# ElectronOnAStick-V1.net
KiCad netlist of a schematic drawn in EAGLE
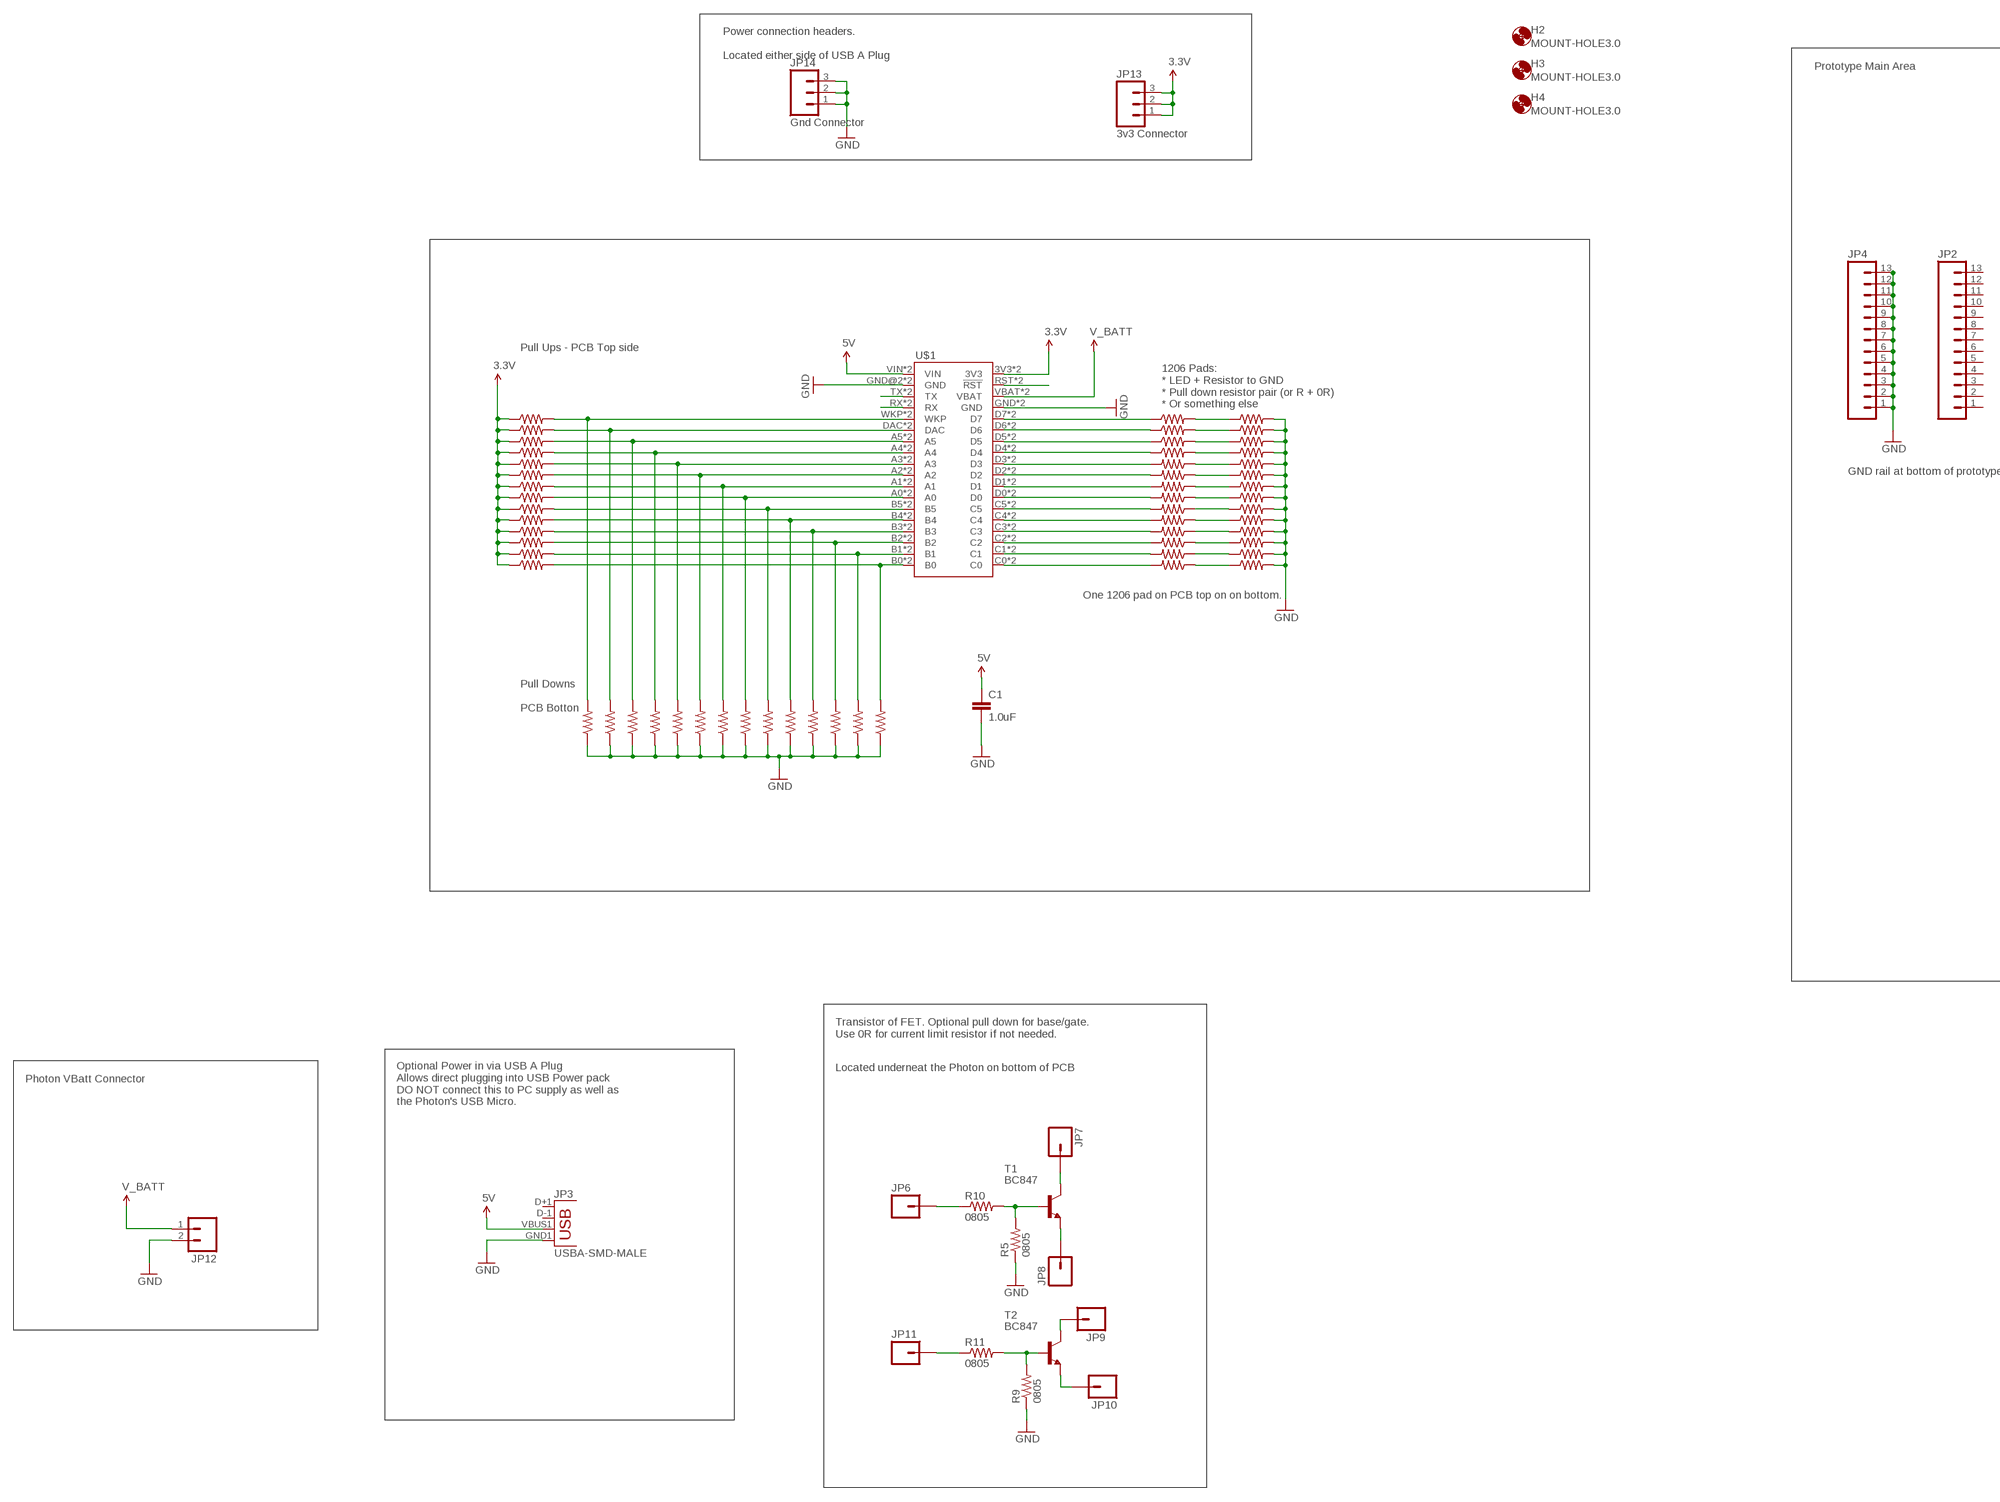
[diagram p0: schematic, sheet 1, part 1 of 2]
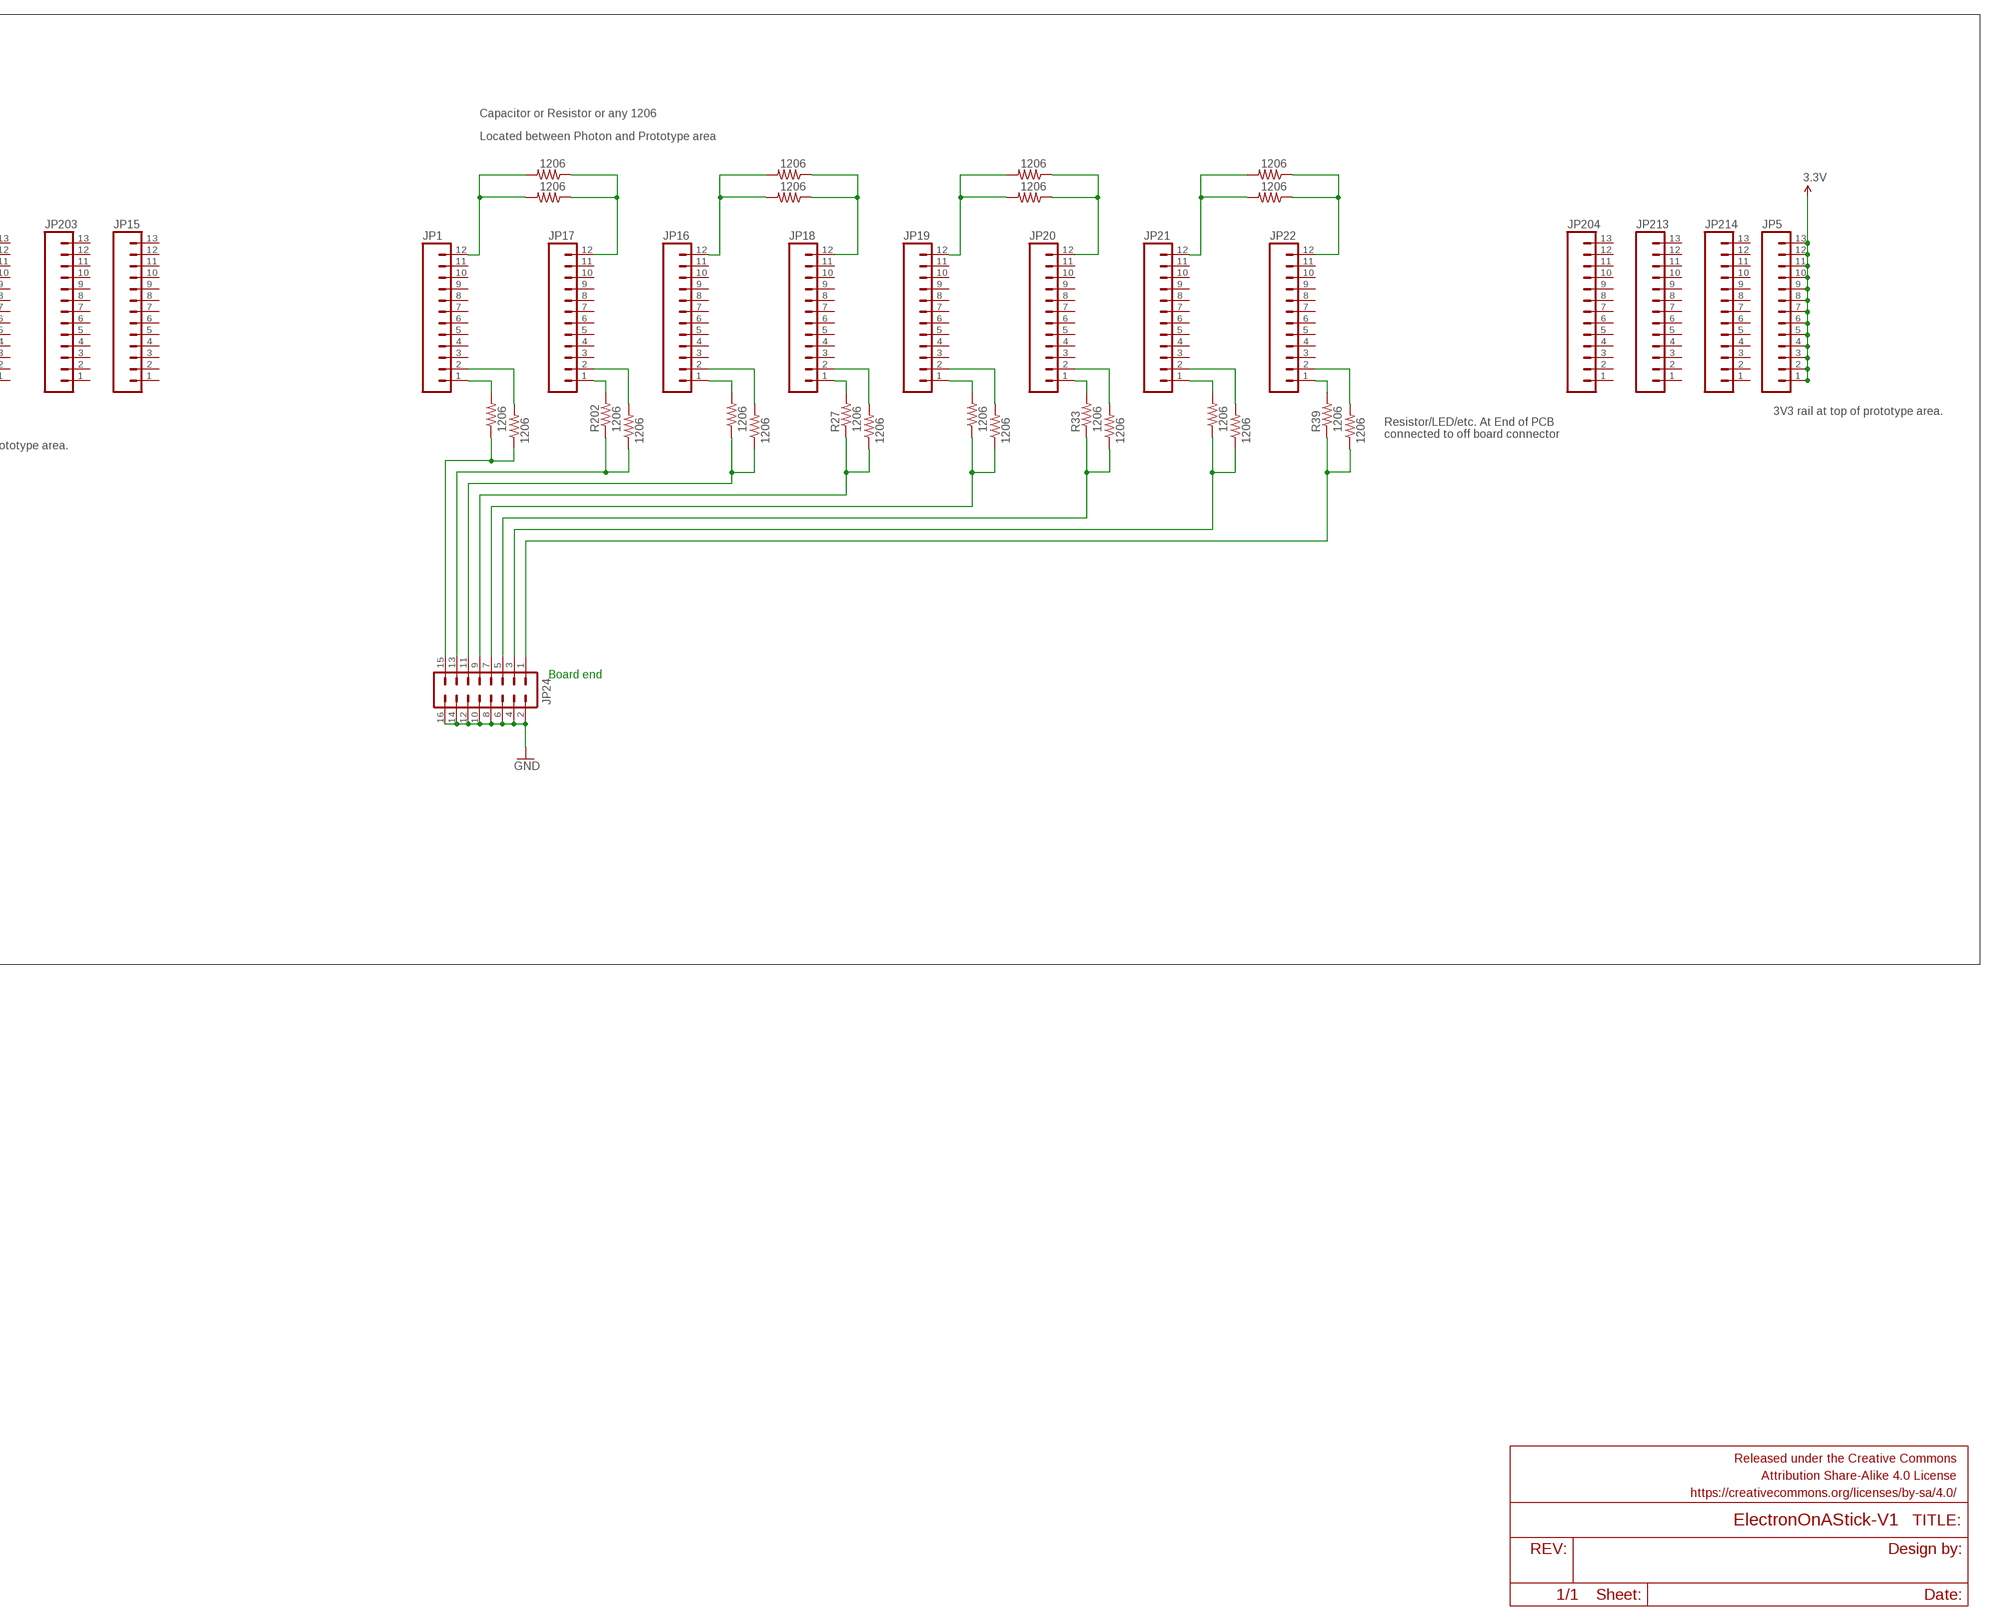
[diagram p1: schematic, sheet 1, part 2 of 2]

(export (version "E")
  (design (tool "Eeschema 10.0.6"))
  (components
    (comp (ref "C1")
      (value "1.0uF")
      (footprint "eagle-import:0805-CAP")
      (libsource (lib "eagle-import") (part "1.0UF-25V-+80/-20(0805){dblquote}"))
    )
    (comp (ref "FRAME1")
      (value "FRAME-LEDGER")
      (footprint "eagle-import:CREATIVE_COMMONS")
      (libsource (lib "eagle-import") (part "FRAME-LEDGER"))
    )
    (comp (ref "H2")
      (value "MOUNT-HOLE3.0")
      (footprint "eagle-import:3,0")
      (libsource (lib "eagle-import") (part "MOUNT-HOLE3.0"))
    )
    (comp (ref "H3")
      (value "MOUNT-HOLE3.0")
      (footprint "eagle-import:3,0")
      (libsource (lib "eagle-import") (part "MOUNT-HOLE3.0"))
    )
    (comp (ref "H4")
      (value "MOUNT-HOLE3.0")
      (footprint "eagle-import:3,0")
      (libsource (lib "eagle-import") (part "MOUNT-HOLE3.0"))
    )
    (comp (ref "JP1")
      (value "M12PTH")
      (footprint "eagle-import:1X12")
      (libsource (lib "eagle-import") (part "M12PTH"))
    )
    (comp (ref "JP2")
      (value "M13")
      (footprint "eagle-import:1X13")
      (libsource (lib "eagle-import") (part "M13"))
    )
    (comp (ref "JP3")
      (value "USBA-SMD-MALE")
      (footprint "eagle-import:USB-A-SMT-MALE")
      (libsource (lib "eagle-import") (part "USBA-SMD-MALE"))
    )
    (comp (ref "JP4")
      (value "M13")
      (footprint "eagle-import:1X13")
      (libsource (lib "eagle-import") (part "M13"))
    )
    (comp (ref "JP5")
      (value "M13")
      (footprint "eagle-import:1X13")
      (libsource (lib "eagle-import") (part "M13"))
    )
    (comp (ref "JP6")
      (value "M01PTH")
      (footprint "eagle-import:1X01")
      (libsource (lib "eagle-import") (part "M01PTH"))
    )
    (comp (ref "JP7")
      (value "M01PTH")
      (footprint "eagle-import:1X01")
      (libsource (lib "eagle-import") (part "M01PTH"))
    )
    (comp (ref "JP8")
      (value "M01PTH")
      (footprint "eagle-import:1X01")
      (libsource (lib "eagle-import") (part "M01PTH"))
    )
    (comp (ref "JP9")
      (value "M01PTH")
      (footprint "eagle-import:1X01")
      (libsource (lib "eagle-import") (part "M01PTH"))
    )
    (comp (ref "JP10")
      (value "M01PTH")
      (footprint "eagle-import:1X01")
      (libsource (lib "eagle-import") (part "M01PTH"))
    )
    (comp (ref "JP11")
      (value "M01PTH")
      (footprint "eagle-import:1X01")
      (libsource (lib "eagle-import") (part "M01PTH"))
    )
    (comp (ref "JP12")
      (value "M02JST-PTH-2")
      (footprint "eagle-import:JST-2-PTH")
      (libsource (lib "eagle-import") (part "M02JST-PTH-2"))
    )
    (comp (ref "JP13")
      (value "3v3 Connector")
      (footprint "eagle-import:1X03")
      (libsource (lib "eagle-import") (part "M03PTH"))
    )
    (comp (ref "JP14")
      (value "Gnd Connector")
      (footprint "eagle-import:1X03")
      (libsource (lib "eagle-import") (part "M03PTH"))
    )
    (comp (ref "JP15")
      (value "M13")
      (footprint "eagle-import:1X13")
      (libsource (lib "eagle-import") (part "M13"))
    )
    (comp (ref "JP16")
      (value "M12PTH")
      (footprint "eagle-import:1X12")
      (libsource (lib "eagle-import") (part "M12PTH"))
    )
    (comp (ref "JP17")
      (value "M12PTH")
      (footprint "eagle-import:1X12")
      (libsource (lib "eagle-import") (part "M12PTH"))
    )
    (comp (ref "JP18")
      (value "M12PTH")
      (footprint "eagle-import:1X12")
      (libsource (lib "eagle-import") (part "M12PTH"))
    )
    (comp (ref "JP19")
      (value "M12PTH")
      (footprint "eagle-import:1X12")
      (libsource (lib "eagle-import") (part "M12PTH"))
    )
    (comp (ref "JP20")
      (value "M12PTH")
      (footprint "eagle-import:1X12")
      (libsource (lib "eagle-import") (part "M12PTH"))
    )
    (comp (ref "JP21")
      (value "M12PTH")
      (footprint "eagle-import:1X12")
      (libsource (lib "eagle-import") (part "M12PTH"))
    )
    (comp (ref "JP22")
      (value "M12PTH")
      (footprint "eagle-import:1X12")
      (libsource (lib "eagle-import") (part "M12PTH"))
    )
    (comp (ref "JP24")
      (value "M08X2")
      (footprint "eagle-import:2X8")
      (libsource (lib "eagle-import") (part "M08X2"))
    )
    (comp (ref "JP203")
      (value "M13")
      (footprint "eagle-import:1X13")
      (libsource (lib "eagle-import") (part "M13"))
    )
    (comp (ref "JP204")
      (value "M13")
      (footprint "eagle-import:1X13")
      (libsource (lib "eagle-import") (part "M13"))
    )
    (comp (ref "JP213")
      (value "M13")
      (footprint "eagle-import:1X13")
      (libsource (lib "eagle-import") (part "M13"))
    )
    (comp (ref "JP214")
      (value "M13")
      (footprint "eagle-import:1X13")
      (libsource (lib "eagle-import") (part "M13"))
    )
    (comp (ref "R1")
      (value "1206")
      (footprint "eagle-import:1206")
      (libsource (lib "eagle-import") (part "RESISTOR1206"))
    )
    (comp (ref "R2")
      (value "1206")
      (footprint "eagle-import:1206")
      (libsource (lib "eagle-import") (part "RESISTOR1206"))
    )
    (comp (ref "R3")
      (value "1206")
      (footprint "eagle-import:1206")
      (libsource (lib "eagle-import") (part "RESISTOR1206"))
    )
    (comp (ref "R4")
      (value "1206")
      (footprint "eagle-import:1206")
      (libsource (lib "eagle-import") (part "RESISTOR1206"))
    )
    (comp (ref "R5")
      (value "0805")
      (footprint "eagle-import:0805")
      (libsource (lib "eagle-import") (part "RESISTOR0805-RES"))
    )
    (comp (ref "R6")
      (value "1206")
      (footprint "eagle-import:1206")
      (libsource (lib "eagle-import") (part "RESISTOR1206"))
    )
    (comp (ref "R7")
      (value "1206")
      (footprint "eagle-import:1206")
      (libsource (lib "eagle-import") (part "RESISTOR1206"))
    )
    (comp (ref "R8")
      (value "1206")
      (footprint "eagle-import:1206")
      (libsource (lib "eagle-import") (part "RESISTOR1206"))
    )
    (comp (ref "R9")
      (value "0805")
      (footprint "eagle-import:0805")
      (libsource (lib "eagle-import") (part "RESISTOR0805-RES"))
    )
    (comp (ref "R10")
      (value "0805")
      (footprint "eagle-import:0805")
      (libsource (lib "eagle-import") (part "RESISTOR0805-RES"))
    )
    (comp (ref "R11")
      (value "0805")
      (footprint "eagle-import:0805")
      (libsource (lib "eagle-import") (part "RESISTOR0805-RES"))
    )
    (comp (ref "R12")
      (value "1206")
      (footprint "eagle-import:1206")
      (libsource (lib "eagle-import") (part "RESISTOR1206"))
    )
    (comp (ref "R13")
      (value "1206")
      (footprint "eagle-import:1206")
      (libsource (lib "eagle-import") (part "RESISTOR1206"))
    )
    (comp (ref "R14")
      (value "1206")
      (footprint "eagle-import:1206")
      (libsource (lib "eagle-import") (part "RESISTOR1206"))
    )
    (comp (ref "R15")
      (value "1206")
      (footprint "eagle-import:1206")
      (libsource (lib "eagle-import") (part "RESISTOR1206"))
    )
    (comp (ref "R16")
      (value "1206")
      (footprint "eagle-import:1206")
      (libsource (lib "eagle-import") (part "RESISTOR1206"))
    )
    (comp (ref "R17")
      (value "1206")
      (footprint "eagle-import:1206")
      (libsource (lib "eagle-import") (part "RESISTOR1206"))
    )
    (comp (ref "R18")
      (value "1206")
      (footprint "eagle-import:1206")
      (libsource (lib "eagle-import") (part "RESISTOR1206"))
    )
    (comp (ref "R19")
      (value "1206")
      (footprint "eagle-import:1206")
      (libsource (lib "eagle-import") (part "RESISTOR1206"))
    )
    (comp (ref "R20")
      (value "1206")
      (footprint "eagle-import:1206")
      (libsource (lib "eagle-import") (part "RESISTOR1206"))
    )
    (comp (ref "R21")
      (value "1206")
      (footprint "eagle-import:1206")
      (libsource (lib "eagle-import") (part "RESISTOR1206"))
    )
    (comp (ref "R22")
      (value "1206")
      (footprint "eagle-import:1206")
      (libsource (lib "eagle-import") (part "RESISTOR1206"))
    )
    (comp (ref "R23")
      (value "1206")
      (footprint "eagle-import:1206")
      (libsource (lib "eagle-import") (part "RESISTOR1206"))
    )
    (comp (ref "R24")
      (value "1206")
      (footprint "eagle-import:1206")
      (libsource (lib "eagle-import") (part "RESISTOR1206"))
    )
    (comp (ref "R25")
      (value "1206")
      (footprint "eagle-import:1206")
      (libsource (lib "eagle-import") (part "RESISTOR1206"))
    )
    (comp (ref "R26")
      (value "1206")
      (footprint "eagle-import:1206")
      (libsource (lib "eagle-import") (part "RESISTOR1206"))
    )
    (comp (ref "R27")
      (value "1206")
      (footprint "eagle-import:1206")
      (libsource (lib "eagle-import") (part "RESISTOR1206"))
    )
    (comp (ref "R28")
      (value "1206")
      (footprint "eagle-import:1206")
      (libsource (lib "eagle-import") (part "RESISTOR1206"))
    )
    (comp (ref "R29")
      (value "1206")
      (footprint "eagle-import:1206")
      (libsource (lib "eagle-import") (part "RESISTOR1206"))
    )
    (comp (ref "R30")
      (value "1206")
      (footprint "eagle-import:1206")
      (libsource (lib "eagle-import") (part "RESISTOR1206"))
    )
    (comp (ref "R31")
      (value "1206")
      (footprint "eagle-import:1206")
      (libsource (lib "eagle-import") (part "RESISTOR1206"))
    )
    (comp (ref "R32")
      (value "1206")
      (footprint "eagle-import:1206")
      (libsource (lib "eagle-import") (part "RESISTOR1206"))
    )
    (comp (ref "R33")
      (value "1206")
      (footprint "eagle-import:1206")
      (libsource (lib "eagle-import") (part "RESISTOR1206"))
    )
    (comp (ref "R34")
      (value "1206")
      (footprint "eagle-import:1206")
      (libsource (lib "eagle-import") (part "RESISTOR1206"))
    )
    (comp (ref "R35")
      (value "1206")
      (footprint "eagle-import:1206")
      (libsource (lib "eagle-import") (part "RESISTOR1206"))
    )
    (comp (ref "R36")
      (value "1206")
      (footprint "eagle-import:1206")
      (libsource (lib "eagle-import") (part "RESISTOR1206"))
    )
    (comp (ref "R37")
      (value "1206")
      (footprint "eagle-import:1206")
      (libsource (lib "eagle-import") (part "RESISTOR1206"))
    )
    (comp (ref "R38")
      (value "1206")
      (footprint "eagle-import:1206")
      (libsource (lib "eagle-import") (part "RESISTOR1206"))
    )
    (comp (ref "R39")
      (value "1206")
      (footprint "eagle-import:1206")
      (libsource (lib "eagle-import") (part "RESISTOR1206"))
    )
    (comp (ref "R40")
      (value "1206")
      (footprint "eagle-import:1206")
      (libsource (lib "eagle-import") (part "RESISTOR1206"))
    )
    (comp (ref "R41")
      (value "1206")
      (footprint "eagle-import:1206")
      (libsource (lib "eagle-import") (part "RESISTOR1206"))
    )
    (comp (ref "R42")
      (value "1206")
      (footprint "eagle-import:1206")
      (libsource (lib "eagle-import") (part "RESISTOR1206"))
    )
    (comp (ref "R43")
      (value "1206")
      (footprint "eagle-import:1206")
      (libsource (lib "eagle-import") (part "RESISTOR1206"))
    )
    (comp (ref "R44")
      (value "1206")
      (footprint "eagle-import:1206")
      (libsource (lib "eagle-import") (part "RESISTOR1206"))
    )
    (comp (ref "R45")
      (value "1206")
      (footprint "eagle-import:1206")
      (libsource (lib "eagle-import") (part "RESISTOR1206"))
    )
    (comp (ref "R46")
      (value "1206")
      (footprint "eagle-import:1206")
      (libsource (lib "eagle-import") (part "RESISTOR1206"))
    )
    (comp (ref "R47")
      (value "1206")
      (footprint "eagle-import:1206")
      (libsource (lib "eagle-import") (part "RESISTOR1206"))
    )
    (comp (ref "R48")
      (value "1206")
      (footprint "eagle-import:1206")
      (libsource (lib "eagle-import") (part "RESISTOR1206"))
    )
    (comp (ref "R49")
      (value "1206")
      (footprint "eagle-import:1206")
      (libsource (lib "eagle-import") (part "RESISTOR1206"))
    )
    (comp (ref "R50")
      (value "1206")
      (footprint "eagle-import:1206")
      (libsource (lib "eagle-import") (part "RESISTOR1206"))
    )
    (comp (ref "R51")
      (value "1206")
      (footprint "eagle-import:1206")
      (libsource (lib "eagle-import") (part "RESISTOR1206"))
    )
    (comp (ref "R52")
      (value "1206")
      (footprint "eagle-import:1206")
      (libsource (lib "eagle-import") (part "RESISTOR1206"))
    )
    (comp (ref "R53")
      (value "1206")
      (footprint "eagle-import:1206")
      (libsource (lib "eagle-import") (part "RESISTOR1206"))
    )
    (comp (ref "R54")
      (value "1206")
      (footprint "eagle-import:1206")
      (libsource (lib "eagle-import") (part "RESISTOR1206"))
    )
    (comp (ref "R55")
      (value "1206")
      (footprint "eagle-import:1206")
      (libsource (lib "eagle-import") (part "RESISTOR1206"))
    )
    (comp (ref "R56")
      (value "1206")
      (footprint "eagle-import:1206")
      (libsource (lib "eagle-import") (part "RESISTOR1206"))
    )
    (comp (ref "R57")
      (value "1206")
      (footprint "eagle-import:1206")
      (libsource (lib "eagle-import") (part "RESISTOR1206"))
    )
    (comp (ref "R58")
      (value "1206")
      (footprint "eagle-import:1206")
      (libsource (lib "eagle-import") (part "RESISTOR1206"))
    )
    (comp (ref "R59")
      (value "1206")
      (footprint "eagle-import:1206")
      (libsource (lib "eagle-import") (part "RESISTOR1206"))
    )
    (comp (ref "R60")
      (value "1206")
      (footprint "eagle-import:1206")
      (libsource (lib "eagle-import") (part "RESISTOR1206"))
    )
    (comp (ref "R61")
      (value "1206")
      (footprint "eagle-import:1206")
      (libsource (lib "eagle-import") (part "RESISTOR1206"))
    )
    (comp (ref "R62")
      (value "1206")
      (footprint "eagle-import:1206")
      (libsource (lib "eagle-import") (part "RESISTOR1206"))
    )
    (comp (ref "R63")
      (value "1206")
      (footprint "eagle-import:1206")
      (libsource (lib "eagle-import") (part "RESISTOR1206"))
    )
    (comp (ref "R64")
      (value "1206")
      (footprint "eagle-import:1206")
      (libsource (lib "eagle-import") (part "RESISTOR1206"))
    )
    (comp (ref "R65")
      (value "1206")
      (footprint "eagle-import:1206")
      (libsource (lib "eagle-import") (part "RESISTOR1206"))
    )
    (comp (ref "R66")
      (value "1206")
      (footprint "eagle-import:1206")
      (libsource (lib "eagle-import") (part "RESISTOR1206"))
    )
    (comp (ref "R67")
      (value "1206")
      (footprint "eagle-import:1206")
      (libsource (lib "eagle-import") (part "RESISTOR1206"))
    )
    (comp (ref "R68")
      (value "1206")
      (footprint "eagle-import:1206")
      (libsource (lib "eagle-import") (part "RESISTOR1206"))
    )
    (comp (ref "R69")
      (value "1206")
      (footprint "eagle-import:1206")
      (libsource (lib "eagle-import") (part "RESISTOR1206"))
    )
    (comp (ref "R70")
      (value "1206")
      (footprint "eagle-import:1206")
      (libsource (lib "eagle-import") (part "RESISTOR1206"))
    )
    (comp (ref "R201")
      (value "1206")
      (footprint "eagle-import:1206")
      (libsource (lib "eagle-import") (part "RESISTOR1206"))
    )
    (comp (ref "R202")
      (value "1206")
      (footprint "eagle-import:1206")
      (libsource (lib "eagle-import") (part "RESISTOR1206"))
    )
    (comp (ref "R313")
      (value "1206")
      (footprint "eagle-import:1206")
      (libsource (lib "eagle-import") (part "RESISTOR1206"))
    )
    (comp (ref "R314")
      (value "1206")
      (footprint "eagle-import:1206")
      (libsource (lib "eagle-import") (part "RESISTOR1206"))
    )
    (comp (ref "R315")
      (value "1206")
      (footprint "eagle-import:1206")
      (libsource (lib "eagle-import") (part "RESISTOR1206"))
    )
    (comp (ref "R316")
      (value "1206")
      (footprint "eagle-import:1206")
      (libsource (lib "eagle-import") (part "RESISTOR1206"))
    )
    (comp (ref "R317")
      (value "1206")
      (footprint "eagle-import:1206")
      (libsource (lib "eagle-import") (part "RESISTOR1206"))
    )
    (comp (ref "R318")
      (value "1206")
      (footprint "eagle-import:1206")
      (libsource (lib "eagle-import") (part "RESISTOR1206"))
    )
    (comp (ref "R319")
      (value "1206")
      (footprint "eagle-import:1206")
      (libsource (lib "eagle-import") (part "RESISTOR1206"))
    )
    (comp (ref "R320")
      (value "1206")
      (footprint "eagle-import:1206")
      (libsource (lib "eagle-import") (part "RESISTOR1206"))
    )
    (comp (ref "R410")
      (value "1206")
      (footprint "eagle-import:1206")
      (libsource (lib "eagle-import") (part "RESISTOR1206"))
    )
    (comp (ref "R411")
      (value "1206")
      (footprint "eagle-import:1206")
      (libsource (lib "eagle-import") (part "RESISTOR1206"))
    )
    (comp (ref "R412")
      (value "1206")
      (footprint "eagle-import:1206")
      (libsource (lib "eagle-import") (part "RESISTOR1206"))
    )
    (comp (ref "R413")
      (value "1206")
      (footprint "eagle-import:1206")
      (libsource (lib "eagle-import") (part "RESISTOR1206"))
    )
    (comp (ref "T1")
      (value "BC847")
      (footprint "eagle-import:SOT23")
      (libsource (lib "eagle-import") (part "BC847"))
    )
    (comp (ref "T2")
      (value "BC847")
      (footprint "eagle-import:SOT23")
      (libsource (lib "eagle-import") (part "BC847"))
    )
    (comp (ref "U$1")
      (value "ELECTRONDUALNAMED")
      (footprint "eagle-import:ELECTRON_SIMPLE_SILK_NAMES_DUAL")
      (libsource (lib "eagle-import") (part "ELECTRONDUALNAMED"))
    )
  )
  (nets
    (net (code "1") (name "3.3V") (class "Default")
      (node (ref "JP13") (pin "1") (pinfunction "1_1") (pintype "passive"))
      (node (ref "JP13") (pin "2") (pinfunction "2_2") (pintype "passive"))
      (node (ref "JP13") (pin "3") (pinfunction "3_3") (pintype "passive"))
      (node (ref "JP5") (pin "1") (pinfunction "1_1") (pintype "passive"))
      (node (ref "JP5") (pin "10") (pinfunction "10_10") (pintype "passive"))
      (node (ref "JP5") (pin "11") (pinfunction "11_11") (pintype "passive"))
      (node (ref "JP5") (pin "12") (pinfunction "12_12") (pintype "passive"))
      (node (ref "JP5") (pin "13") (pinfunction "13_13") (pintype "passive"))
      (node (ref "JP5") (pin "2") (pinfunction "2_2") (pintype "passive"))
      (node (ref "JP5") (pin "3") (pinfunction "3_3") (pintype "passive"))
      (node (ref "JP5") (pin "4") (pinfunction "4_4") (pintype "passive"))
      (node (ref "JP5") (pin "5") (pinfunction "5_5") (pintype "passive"))
      (node (ref "JP5") (pin "6") (pinfunction "6_6") (pintype "passive"))
      (node (ref "JP5") (pin "7") (pinfunction "7_7") (pintype "passive"))
      (node (ref "JP5") (pin "8") (pinfunction "8_8") (pintype "passive"))
      (node (ref "JP5") (pin "9") (pinfunction "9_9") (pintype "passive"))
      (node (ref "R1") (pin "1") (pinfunction "1_1") (pintype "passive"))
      (node (ref "R12") (pin "1") (pinfunction "1_1") (pintype "passive"))
      (node (ref "R2") (pin "1") (pinfunction "1_1") (pintype "passive"))
      (node (ref "R3") (pin "1") (pinfunction "1_1") (pintype "passive"))
      (node (ref "R4") (pin "1") (pinfunction "1_1") (pintype "passive"))
      (node (ref "R45") (pin "1") (pinfunction "1_1") (pintype "passive"))
      (node (ref "R46") (pin "1") (pinfunction "1_1") (pintype "passive"))
      (node (ref "R47") (pin "1") (pinfunction "1_1") (pintype "passive"))
      (node (ref "R48") (pin "1") (pinfunction "1_1") (pintype "passive"))
      (node (ref "R49") (pin "1") (pinfunction "1_1") (pintype "passive"))
      (node (ref "R6") (pin "1") (pinfunction "1_1") (pintype "passive"))
      (node (ref "R67") (pin "1") (pinfunction "1_1") (pintype "passive"))
      (node (ref "R68") (pin "1") (pinfunction "1_1") (pintype "passive"))
      (node (ref "R7") (pin "1") (pinfunction "1_1") (pintype "passive"))
      (node (ref "U$1") (pin "3V3") (pinfunction "3V3_3V3") (pintype "power_in"))
      (node (ref "U$1") (pin "3V3_1") (pinfunction "3V3_3V3_1") (pintype "power_in"))
    )
    (net (code "2") (name "5V") (class "Default")
      (node (ref "C1") (pin "1") (pinfunction "1_1") (pintype "passive"))
      (node (ref "JP3") (pin "VBUS1") (pinfunction "VBUS_VBUS1") (pintype "bidirectional"))
      (node (ref "U$1") (pin "VIN") (pinfunction "VIN_VIN") (pintype "power_in"))
      (node (ref "U$1") (pin "VIN_1B") (pinfunction "VIN_VIN_1B") (pintype "power_in"))
    )
    (net (code "3") (name "GND") (class "Default")
      (node (ref "C1") (pin "2") (pinfunction "2_2") (pintype "passive"))
      (node (ref "JP12") (pin "2") (pinfunction "2_2") (pintype "passive"))
      (node (ref "JP14") (pin "1") (pinfunction "1_1") (pintype "passive"))
      (node (ref "JP14") (pin "2") (pinfunction "2_2") (pintype "passive"))
      (node (ref "JP14") (pin "3") (pinfunction "3_3") (pintype "passive"))
      (node (ref "JP24") (pin "10") (pinfunction "10_10") (pintype "passive"))
      (node (ref "JP24") (pin "12") (pinfunction "12_12") (pintype "passive"))
      (node (ref "JP24") (pin "14") (pinfunction "14_14") (pintype "passive"))
      (node (ref "JP24") (pin "16") (pinfunction "16_16") (pintype "passive"))
      (node (ref "JP24") (pin "2") (pinfunction "2_2") (pintype "passive"))
      (node (ref "JP24") (pin "4") (pinfunction "4_4") (pintype "passive"))
      (node (ref "JP24") (pin "6") (pinfunction "6_6") (pintype "passive"))
      (node (ref "JP24") (pin "8") (pinfunction "8_8") (pintype "passive"))
      (node (ref "JP3") (pin "GND1") (pinfunction "GND_GND1") (pintype "bidirectional"))
      (node (ref "JP4") (pin "1") (pinfunction "1_1") (pintype "passive"))
      (node (ref "JP4") (pin "10") (pinfunction "10_10") (pintype "passive"))
      (node (ref "JP4") (pin "11") (pinfunction "11_11") (pintype "passive"))
      (node (ref "JP4") (pin "12") (pinfunction "12_12") (pintype "passive"))
      (node (ref "JP4") (pin "13") (pinfunction "13_13") (pintype "passive"))
      (node (ref "JP4") (pin "2") (pinfunction "2_2") (pintype "passive"))
      (node (ref "JP4") (pin "3") (pinfunction "3_3") (pintype "passive"))
      (node (ref "JP4") (pin "4") (pinfunction "4_4") (pintype "passive"))
      (node (ref "JP4") (pin "5") (pinfunction "5_5") (pintype "passive"))
      (node (ref "JP4") (pin "6") (pinfunction "6_6") (pintype "passive"))
      (node (ref "JP4") (pin "7") (pinfunction "7_7") (pintype "passive"))
      (node (ref "JP4") (pin "8") (pinfunction "8_8") (pintype "passive"))
      (node (ref "JP4") (pin "9") (pinfunction "9_9") (pintype "passive"))
      (node (ref "R13") (pin "1") (pinfunction "1_1") (pintype "passive"))
      (node (ref "R14") (pin "1") (pinfunction "1_1") (pintype "passive"))
      (node (ref "R15") (pin "2") (pinfunction "2_2") (pintype "passive"))
      (node (ref "R16") (pin "2") (pinfunction "2_2") (pintype "passive"))
      (node (ref "R17") (pin "2") (pinfunction "2_2") (pintype "passive"))
      (node (ref "R18") (pin "2") (pinfunction "2_2") (pintype "passive"))
      (node (ref "R19") (pin "1") (pinfunction "1_1") (pintype "passive"))
      (node (ref "R20") (pin "1") (pinfunction "1_1") (pintype "passive"))
      (node (ref "R21") (pin "1") (pinfunction "1_1") (pintype "passive"))
      (node (ref "R22") (pin "1") (pinfunction "1_1") (pintype "passive"))
      (node (ref "R410") (pin "2") (pinfunction "2_2") (pintype "passive"))
      (node (ref "R411") (pin "2") (pinfunction "2_2") (pintype "passive"))
      (node (ref "R412") (pin "2") (pinfunction "2_2") (pintype "passive"))
      (node (ref "R413") (pin "2") (pinfunction "2_2") (pintype "passive"))
      (node (ref "R5") (pin "1") (pinfunction "1_1") (pintype "passive"))
      (node (ref "R50") (pin "1") (pinfunction "1_1") (pintype "passive"))
      (node (ref "R51") (pin "1") (pinfunction "1_1") (pintype "passive"))
      (node (ref "R52") (pin "1") (pinfunction "1_1") (pintype "passive"))
      (node (ref "R53") (pin "1") (pinfunction "1_1") (pintype "passive"))
      (node (ref "R54") (pin "1") (pinfunction "1_1") (pintype "passive"))
      (node (ref "R55") (pin "2") (pinfunction "2_2") (pintype "passive"))
      (node (ref "R56") (pin "2") (pinfunction "2_2") (pintype "passive"))
      (node (ref "R57") (pin "2") (pinfunction "2_2") (pintype "passive"))
      (node (ref "R58") (pin "2") (pinfunction "2_2") (pintype "passive"))
      (node (ref "R59") (pin "2") (pinfunction "2_2") (pintype "passive"))
      (node (ref "R60") (pin "2") (pinfunction "2_2") (pintype "passive"))
      (node (ref "R69") (pin "1") (pinfunction "1_1") (pintype "passive"))
      (node (ref "R70") (pin "1") (pinfunction "1_1") (pintype "passive"))
      (node (ref "R8") (pin "1") (pinfunction "1_1") (pintype "passive"))
      (node (ref "R9") (pin "1") (pinfunction "1_1") (pintype "passive"))
      (node (ref "U$1") (pin "GND") (pinfunction "GND_GND") (pintype "power_in"))
      (node (ref "U$1") (pin "GND@2") (pinfunction "GND_GND@2") (pintype "power_in"))
      (node (ref "U$1") (pin "GND_1") (pinfunction "GND_GND_1") (pintype "power_in"))
      (node (ref "U$1") (pin "GND_1B") (pinfunction "GND_GND_1B") (pintype "power_in"))
    )
    (net (code "4") (name "Net-(JP1-Pad1)") (class "Default")
      (node (ref "JP1") (pin "1") (pinfunction "1_1") (pintype "passive"))
      (node (ref "R201") (pin "2") (pinfunction "2_2") (pintype "passive"))
    )
    (net (code "5") (name "Net-(JP1-Pad2)") (class "Default")
      (node (ref "JP1") (pin "2") (pinfunction "2_2") (pintype "passive"))
      (node (ref "R23") (pin "2") (pinfunction "2_2") (pintype "passive"))
    )
    (net (code "6") (name "Net-(JP1-Pad12)") (class "Default")
      (node (ref "JP1") (pin "12") (pinfunction "12_12") (pintype "passive"))
      (node (ref "R24") (pin "2") (pinfunction "2_2") (pintype "passive"))
      (node (ref "R25") (pin "2") (pinfunction "2_2") (pintype "passive"))
    )
    (net (code "7") (name "Net-(JP6-Pad1)") (class "Default")
      (node (ref "JP6") (pin "1") (pinfunction "1_1") (pintype "passive"))
      (node (ref "R10") (pin "1") (pinfunction "1_1") (pintype "passive"))
    )
    (net (code "8") (name "Net-(JP11-Pad1)") (class "Default")
      (node (ref "JP11") (pin "1") (pinfunction "1_1") (pintype "passive"))
      (node (ref "R11") (pin "1") (pinfunction "1_1") (pintype "passive"))
    )
    (net (code "9") (name "Net-(JP16-Pad1)") (class "Default")
      (node (ref "JP16") (pin "1") (pinfunction "1_1") (pintype "passive"))
      (node (ref "R28") (pin "2") (pinfunction "2_2") (pintype "passive"))
    )
    (net (code "10") (name "Net-(JP16-Pad2)") (class "Default")
      (node (ref "JP16") (pin "2") (pinfunction "2_2") (pintype "passive"))
      (node (ref "R29") (pin "2") (pinfunction "2_2") (pintype "passive"))
    )
    (net (code "11") (name "Net-(JP16-Pad12)") (class "Default")
      (node (ref "JP16") (pin "12") (pinfunction "12_12") (pintype "passive"))
      (node (ref "R30") (pin "2") (pinfunction "2_2") (pintype "passive"))
      (node (ref "R31") (pin "2") (pinfunction "2_2") (pintype "passive"))
    )
    (net (code "12") (name "Net-(JP17-Pad1)") (class "Default")
      (node (ref "JP17") (pin "1") (pinfunction "1_1") (pintype "passive"))
      (node (ref "R202") (pin "2") (pinfunction "2_2") (pintype "passive"))
    )
    (net (code "13") (name "Net-(JP17-Pad2)") (class "Default")
      (node (ref "JP17") (pin "2") (pinfunction "2_2") (pintype "passive"))
      (node (ref "R26") (pin "2") (pinfunction "2_2") (pintype "passive"))
    )
    (net (code "14") (name "Net-(JP17-Pad12)") (class "Default")
      (node (ref "JP17") (pin "12") (pinfunction "12_12") (pintype "passive"))
      (node (ref "R24") (pin "1") (pinfunction "1_1") (pintype "passive"))
      (node (ref "R25") (pin "1") (pinfunction "1_1") (pintype "passive"))
    )
    (net (code "15") (name "Net-(JP18-Pad1)") (class "Default")
      (node (ref "JP18") (pin "1") (pinfunction "1_1") (pintype "passive"))
      (node (ref "R27") (pin "2") (pinfunction "2_2") (pintype "passive"))
    )
    (net (code "16") (name "Net-(JP18-Pad2)") (class "Default")
      (node (ref "JP18") (pin "2") (pinfunction "2_2") (pintype "passive"))
      (node (ref "R32") (pin "2") (pinfunction "2_2") (pintype "passive"))
    )
    (net (code "17") (name "Net-(JP18-Pad12)") (class "Default")
      (node (ref "JP18") (pin "12") (pinfunction "12_12") (pintype "passive"))
      (node (ref "R30") (pin "1") (pinfunction "1_1") (pintype "passive"))
      (node (ref "R31") (pin "1") (pinfunction "1_1") (pintype "passive"))
    )
    (net (code "18") (name "Net-(JP19-Pad1)") (class "Default")
      (node (ref "JP19") (pin "1") (pinfunction "1_1") (pintype "passive"))
      (node (ref "R34") (pin "2") (pinfunction "2_2") (pintype "passive"))
    )
    (net (code "19") (name "Net-(JP19-Pad2)") (class "Default")
      (node (ref "JP19") (pin "2") (pinfunction "2_2") (pintype "passive"))
      (node (ref "R35") (pin "2") (pinfunction "2_2") (pintype "passive"))
    )
    (net (code "20") (name "Net-(JP19-Pad12)") (class "Default")
      (node (ref "JP19") (pin "12") (pinfunction "12_12") (pintype "passive"))
      (node (ref "R36") (pin "2") (pinfunction "2_2") (pintype "passive"))
      (node (ref "R37") (pin "2") (pinfunction "2_2") (pintype "passive"))
    )
    (net (code "21") (name "Net-(JP20-Pad1)") (class "Default")
      (node (ref "JP20") (pin "1") (pinfunction "1_1") (pintype "passive"))
      (node (ref "R33") (pin "2") (pinfunction "2_2") (pintype "passive"))
    )
    (net (code "22") (name "Net-(JP20-Pad2)") (class "Default")
      (node (ref "JP20") (pin "2") (pinfunction "2_2") (pintype "passive"))
      (node (ref "R38") (pin "2") (pinfunction "2_2") (pintype "passive"))
    )
    (net (code "23") (name "Net-(JP20-Pad12)") (class "Default")
      (node (ref "JP20") (pin "12") (pinfunction "12_12") (pintype "passive"))
      (node (ref "R36") (pin "1") (pinfunction "1_1") (pintype "passive"))
      (node (ref "R37") (pin "1") (pinfunction "1_1") (pintype "passive"))
    )
    (net (code "24") (name "Net-(JP21-Pad1)") (class "Default")
      (node (ref "JP21") (pin "1") (pinfunction "1_1") (pintype "passive"))
      (node (ref "R40") (pin "2") (pinfunction "2_2") (pintype "passive"))
    )
    (net (code "25") (name "Net-(JP21-Pad2)") (class "Default")
      (node (ref "JP21") (pin "2") (pinfunction "2_2") (pintype "passive"))
      (node (ref "R41") (pin "2") (pinfunction "2_2") (pintype "passive"))
    )
    (net (code "26") (name "Net-(JP21-Pad12)") (class "Default")
      (node (ref "JP21") (pin "12") (pinfunction "12_12") (pintype "passive"))
      (node (ref "R42") (pin "2") (pinfunction "2_2") (pintype "passive"))
      (node (ref "R43") (pin "2") (pinfunction "2_2") (pintype "passive"))
    )
    (net (code "27") (name "Net-(JP22-Pad1)") (class "Default")
      (node (ref "JP22") (pin "1") (pinfunction "1_1") (pintype "passive"))
      (node (ref "R39") (pin "2") (pinfunction "2_2") (pintype "passive"))
    )
    (net (code "28") (name "Net-(JP22-Pad2)") (class "Default")
      (node (ref "JP22") (pin "2") (pinfunction "2_2") (pintype "passive"))
      (node (ref "R44") (pin "2") (pinfunction "2_2") (pintype "passive"))
    )
    (net (code "29") (name "Net-(JP22-Pad12)") (class "Default")
      (node (ref "JP22") (pin "12") (pinfunction "12_12") (pintype "passive"))
      (node (ref "R42") (pin "1") (pinfunction "1_1") (pintype "passive"))
      (node (ref "R43") (pin "1") (pinfunction "1_1") (pintype "passive"))
    )
    (net (code "30") (name "Net-(JP24-Pad1)") (class "Default")
      (node (ref "JP24") (pin "1") (pinfunction "1_1") (pintype "passive"))
      (node (ref "R39") (pin "1") (pinfunction "1_1") (pintype "passive"))
      (node (ref "R44") (pin "1") (pinfunction "1_1") (pintype "passive"))
    )
    (net (code "31") (name "Net-(JP24-Pad3)") (class "Default")
      (node (ref "JP24") (pin "3") (pinfunction "3_3") (pintype "passive"))
      (node (ref "R40") (pin "1") (pinfunction "1_1") (pintype "passive"))
      (node (ref "R41") (pin "1") (pinfunction "1_1") (pintype "passive"))
    )
    (net (code "32") (name "Net-(JP24-Pad5)") (class "Default")
      (node (ref "JP24") (pin "5") (pinfunction "5_5") (pintype "passive"))
      (node (ref "R33") (pin "1") (pinfunction "1_1") (pintype "passive"))
      (node (ref "R38") (pin "1") (pinfunction "1_1") (pintype "passive"))
    )
    (net (code "33") (name "Net-(JP24-Pad7)") (class "Default")
      (node (ref "JP24") (pin "7") (pinfunction "7_7") (pintype "passive"))
      (node (ref "R34") (pin "1") (pinfunction "1_1") (pintype "passive"))
      (node (ref "R35") (pin "1") (pinfunction "1_1") (pintype "passive"))
    )
    (net (code "34") (name "Net-(JP24-Pad9)") (class "Default")
      (node (ref "JP24") (pin "9") (pinfunction "9_9") (pintype "passive"))
      (node (ref "R27") (pin "1") (pinfunction "1_1") (pintype "passive"))
      (node (ref "R32") (pin "1") (pinfunction "1_1") (pintype "passive"))
    )
    (net (code "35") (name "Net-(JP24-Pad11)") (class "Default")
      (node (ref "JP24") (pin "11") (pinfunction "11_11") (pintype "passive"))
      (node (ref "R28") (pin "1") (pinfunction "1_1") (pintype "passive"))
      (node (ref "R29") (pin "1") (pinfunction "1_1") (pintype "passive"))
    )
    (net (code "36") (name "Net-(JP24-Pad13)") (class "Default")
      (node (ref "JP24") (pin "13") (pinfunction "13_13") (pintype "passive"))
      (node (ref "R202") (pin "1") (pinfunction "1_1") (pintype "passive"))
      (node (ref "R26") (pin "1") (pinfunction "1_1") (pintype "passive"))
    )
    (net (code "37") (name "Net-(JP24-Pad15)") (class "Default")
      (node (ref "JP24") (pin "15") (pinfunction "15_15") (pintype "passive"))
      (node (ref "R201") (pin "1") (pinfunction "1_1") (pintype "passive"))
      (node (ref "R23") (pin "1") (pinfunction "1_1") (pintype "passive"))
    )
    (net (code "38") (name "Net-(R1-Pad2)") (class "Default")
      (node (ref "R1") (pin "2") (pinfunction "2_2") (pintype "passive"))
      (node (ref "R13") (pin "2") (pinfunction "2_2") (pintype "passive"))
      (node (ref "U$1") (pin "A4") (pinfunction "A4_A4") (pintype "bidirectional"))
      (node (ref "U$1") (pin "A4_1") (pinfunction "A4_A4_1") (pintype "bidirectional"))
    )
    (net (code "39") (name "Net-(R12-Pad2)") (class "Default")
      (node (ref "R12") (pin "2") (pinfunction "2_2") (pintype "passive"))
      (node (ref "R8") (pin "2") (pinfunction "2_2") (pintype "passive"))
      (node (ref "U$1") (pin "A5") (pinfunction "A5_A5") (pintype "bidirectional"))
      (node (ref "U$1") (pin "A5_1") (pinfunction "A5_A5_1") (pintype "bidirectional"))
    )
    (net (code "40") (name "Net-(R14-Pad2)") (class "Default")
      (node (ref "R14") (pin "2") (pinfunction "2_2") (pintype "passive"))
      (node (ref "R2") (pin "2") (pinfunction "2_2") (pintype "passive"))
      (node (ref "U$1") (pin "A3") (pinfunction "A3_A3") (pintype "bidirectional"))
      (node (ref "U$1") (pin "A3_1") (pinfunction "A3_A3_1") (pintype "bidirectional"))
    )
    (net (code "41") (name "Net-(R15-Pad1)") (class "Default")
      (node (ref "R15") (pin "1") (pinfunction "1_1") (pintype "passive"))
      (node (ref "R316") (pin "1") (pinfunction "1_1") (pintype "passive"))
    )
    (net (code "42") (name "Net-(R16-Pad1)") (class "Default")
      (node (ref "R16") (pin "1") (pinfunction "1_1") (pintype "passive"))
      (node (ref "R315") (pin "1") (pinfunction "1_1") (pintype "passive"))
    )
    (net (code "43") (name "Net-(R17-Pad1)") (class "Default")
      (node (ref "R17") (pin "1") (pinfunction "1_1") (pintype "passive"))
      (node (ref "R314") (pin "1") (pinfunction "1_1") (pintype "passive"))
    )
    (net (code "44") (name "Net-(R18-Pad1)") (class "Default")
      (node (ref "R18") (pin "1") (pinfunction "1_1") (pintype "passive"))
      (node (ref "R313") (pin "1") (pinfunction "1_1") (pintype "passive"))
    )
    (net (code "45") (name "Net-(R19-Pad2)") (class "Default")
      (node (ref "R19") (pin "2") (pinfunction "2_2") (pintype "passive"))
      (node (ref "R3") (pin "2") (pinfunction "2_2") (pintype "passive"))
      (node (ref "U$1") (pin "A2") (pinfunction "A2_A2") (pintype "bidirectional"))
      (node (ref "U$1") (pin "A2_1") (pinfunction "A2_A2_1") (pintype "bidirectional"))
    )
    (net (code "46") (name "Net-(R20-Pad2)") (class "Default")
      (node (ref "R20") (pin "2") (pinfunction "2_2") (pintype "passive"))
      (node (ref "R4") (pin "2") (pinfunction "2_2") (pintype "passive"))
      (node (ref "U$1") (pin "A1") (pinfunction "A1_A1") (pintype "bidirectional"))
      (node (ref "U$1") (pin "A1_1") (pinfunction "A1_A1_1") (pintype "bidirectional"))
    )
    (net (code "47") (name "Net-(R21-Pad2)") (class "Default")
      (node (ref "R21") (pin "2") (pinfunction "2_2") (pintype "passive"))
      (node (ref "R6") (pin "2") (pinfunction "2_2") (pintype "passive"))
      (node (ref "U$1") (pin "A0") (pinfunction "A0_A0") (pintype "bidirectional"))
      (node (ref "U$1") (pin "A0_1") (pinfunction "A0_A0_1") (pintype "bidirectional"))
    )
    (net (code "48") (name "Net-(R22-Pad2)") (class "Default")
      (node (ref "R22") (pin "2") (pinfunction "2_2") (pintype "passive"))
      (node (ref "R47") (pin "2") (pinfunction "2_2") (pintype "passive"))
      (node (ref "U$1") (pin "B2") (pinfunction "B2_B2") (pintype "bidirectional"))
      (node (ref "U$1") (pin "B2_1") (pinfunction "B2_B2_1") (pintype "bidirectional"))
    )
    (net (code "49") (name "Net-(R45-Pad2)") (class "Default")
      (node (ref "R45") (pin "2") (pinfunction "2_2") (pintype "passive"))
      (node (ref "R51") (pin "2") (pinfunction "2_2") (pintype "passive"))
      (node (ref "U$1") (pin "B4") (pinfunction "B4_B4") (pintype "bidirectional"))
      (node (ref "U$1") (pin "B4_1") (pinfunction "B4_B4_1") (pintype "bidirectional"))
    )
    (net (code "50") (name "Net-(R46-Pad2)") (class "Default")
      (node (ref "R46") (pin "2") (pinfunction "2_2") (pintype "passive"))
      (node (ref "R52") (pin "2") (pinfunction "2_2") (pintype "passive"))
      (node (ref "U$1") (pin "B3") (pinfunction "B3_B3") (pintype "bidirectional"))
      (node (ref "U$1") (pin "B3_1") (pinfunction "B3_B3_1") (pintype "bidirectional"))
    )
    (net (code "51") (name "Net-(R48-Pad2)") (class "Default")
      (node (ref "R48") (pin "2") (pinfunction "2_2") (pintype "passive"))
      (node (ref "R53") (pin "2") (pinfunction "2_2") (pintype "passive"))
      (node (ref "U$1") (pin "B1") (pinfunction "B1_B1") (pintype "bidirectional"))
      (node (ref "U$1") (pin "B1_1") (pinfunction "B1_B1_1") (pintype "bidirectional"))
    )
    (net (code "52") (name "Net-(R49-Pad2)") (class "Default")
      (node (ref "R49") (pin "2") (pinfunction "2_2") (pintype "passive"))
      (node (ref "R54") (pin "2") (pinfunction "2_2") (pintype "passive"))
      (node (ref "U$1") (pin "B0") (pinfunction "B0_B0") (pintype "bidirectional"))
      (node (ref "U$1") (pin "B0_1") (pinfunction "B0_B0_1") (pintype "bidirectional"))
    )
    (net (code "53") (name "Net-(R50-Pad2)") (class "Default")
      (node (ref "R50") (pin "2") (pinfunction "2_2") (pintype "passive"))
      (node (ref "R7") (pin "2") (pinfunction "2_2") (pintype "passive"))
      (node (ref "U$1") (pin "B5") (pinfunction "B5_B5") (pintype "bidirectional"))
      (node (ref "U$1") (pin "B5_1") (pinfunction "B5_B5_1") (pintype "bidirectional"))
    )
    (net (code "54") (name "Net-(R55-Pad1)") (class "Default")
      (node (ref "R55") (pin "1") (pinfunction "1_1") (pintype "passive"))
      (node (ref "R61") (pin "1") (pinfunction "1_1") (pintype "passive"))
    )
    (net (code "55") (name "Net-(R56-Pad1)") (class "Default")
      (node (ref "R56") (pin "1") (pinfunction "1_1") (pintype "passive"))
      (node (ref "R62") (pin "1") (pinfunction "1_1") (pintype "passive"))
    )
    (net (code "56") (name "Net-(R57-Pad1)") (class "Default")
      (node (ref "R57") (pin "1") (pinfunction "1_1") (pintype "passive"))
      (node (ref "R63") (pin "1") (pinfunction "1_1") (pintype "passive"))
    )
    (net (code "57") (name "Net-(R58-Pad1)") (class "Default")
      (node (ref "R58") (pin "1") (pinfunction "1_1") (pintype "passive"))
      (node (ref "R64") (pin "1") (pinfunction "1_1") (pintype "passive"))
    )
    (net (code "58") (name "Net-(R59-Pad1)") (class "Default")
      (node (ref "R59") (pin "1") (pinfunction "1_1") (pintype "passive"))
      (node (ref "R65") (pin "1") (pinfunction "1_1") (pintype "passive"))
    )
    (net (code "59") (name "Net-(R60-Pad1)") (class "Default")
      (node (ref "R60") (pin "1") (pinfunction "1_1") (pintype "passive"))
      (node (ref "R66") (pin "1") (pinfunction "1_1") (pintype "passive"))
    )
    (net (code "60") (name "Net-(R61-Pad2)") (class "Default")
      (node (ref "R61") (pin "2") (pinfunction "2_2") (pintype "passive"))
      (node (ref "U$1") (pin "C5") (pinfunction "C5_C5") (pintype "bidirectional"))
      (node (ref "U$1") (pin "C5_1") (pinfunction "C5_C5_1") (pintype "bidirectional"))
    )
    (net (code "61") (name "Net-(R62-Pad2)") (class "Default")
      (node (ref "R62") (pin "2") (pinfunction "2_2") (pintype "passive"))
      (node (ref "U$1") (pin "C4") (pinfunction "C4_C4") (pintype "bidirectional"))
      (node (ref "U$1") (pin "C4_1") (pinfunction "C4_C4_1") (pintype "bidirectional"))
    )
    (net (code "62") (name "Net-(R63-Pad2)") (class "Default")
      (node (ref "R63") (pin "2") (pinfunction "2_2") (pintype "passive"))
      (node (ref "U$1") (pin "C3") (pinfunction "C3_C3") (pintype "bidirectional"))
      (node (ref "U$1") (pin "C3_1") (pinfunction "C3_C3_1") (pintype "bidirectional"))
    )
    (net (code "63") (name "Net-(R64-Pad2)") (class "Default")
      (node (ref "R64") (pin "2") (pinfunction "2_2") (pintype "passive"))
      (node (ref "U$1") (pin "C2") (pinfunction "C2_C2") (pintype "bidirectional"))
      (node (ref "U$1") (pin "C2_1") (pinfunction "C2_C2_1") (pintype "bidirectional"))
    )
    (net (code "64") (name "Net-(R65-Pad2)") (class "Default")
      (node (ref "R65") (pin "2") (pinfunction "2_2") (pintype "passive"))
      (node (ref "U$1") (pin "C1") (pinfunction "C1_C1") (pintype "bidirectional"))
      (node (ref "U$1") (pin "C1_1") (pinfunction "C1_C1_1") (pintype "bidirectional"))
    )
    (net (code "65") (name "Net-(R66-Pad2)") (class "Default")
      (node (ref "R66") (pin "2") (pinfunction "2_2") (pintype "passive"))
      (node (ref "U$1") (pin "C0") (pinfunction "C0_C0") (pintype "bidirectional"))
      (node (ref "U$1") (pin "C0_1") (pinfunction "C0_C0_1") (pintype "bidirectional"))
    )
    (net (code "66") (name "Net-(R67-Pad2)") (class "Default")
      (node (ref "R67") (pin "2") (pinfunction "2_2") (pintype "passive"))
      (node (ref "R69") (pin "2") (pinfunction "2_2") (pintype "passive"))
      (node (ref "U$1") (pin "DAC") (pinfunction "DAC_DAC") (pintype "bidirectional"))
      (node (ref "U$1") (pin "DAC_1") (pinfunction "DAC_DAC_1") (pintype "bidirectional"))
    )
    (net (code "67") (name "Net-(R68-Pad2)") (class "Default")
      (node (ref "R68") (pin "2") (pinfunction "2_2") (pintype "passive"))
      (node (ref "R70") (pin "2") (pinfunction "2_2") (pintype "passive"))
      (node (ref "U$1") (pin "WKP") (pinfunction "WKP_WKP") (pintype "bidirectional"))
      (node (ref "U$1") (pin "WKP_1") (pinfunction "WKP_WKP_1") (pintype "bidirectional"))
    )
    (net (code "68") (name "Net-(R313-Pad2)") (class "Default")
      (node (ref "R313") (pin "2") (pinfunction "2_2") (pintype "passive"))
      (node (ref "U$1") (pin "D0") (pinfunction "D0_D0") (pintype "bidirectional"))
      (node (ref "U$1") (pin "D0_1") (pinfunction "D0_D0_1") (pintype "bidirectional"))
    )
    (net (code "69") (name "Net-(R314-Pad2)") (class "Default")
      (node (ref "R314") (pin "2") (pinfunction "2_2") (pintype "passive"))
      (node (ref "U$1") (pin "D1") (pinfunction "D1_D1") (pintype "bidirectional"))
      (node (ref "U$1") (pin "D1_1") (pinfunction "D1_D1_1") (pintype "bidirectional"))
    )
    (net (code "70") (name "Net-(R315-Pad2)") (class "Default")
      (node (ref "R315") (pin "2") (pinfunction "2_2") (pintype "passive"))
      (node (ref "U$1") (pin "D2") (pinfunction "D2_D2") (pintype "bidirectional"))
      (node (ref "U$1") (pin "D2_1") (pinfunction "D2_D2_1") (pintype "bidirectional"))
    )
    (net (code "71") (name "Net-(R316-Pad2)") (class "Default")
      (node (ref "R316") (pin "2") (pinfunction "2_2") (pintype "passive"))
      (node (ref "U$1") (pin "D3") (pinfunction "D3_D3") (pintype "bidirectional"))
      (node (ref "U$1") (pin "D3_1") (pinfunction "D3_D3_1") (pintype "bidirectional"))
    )
    (net (code "72") (name "Net-(R317-Pad1)") (class "Default")
      (node (ref "R317") (pin "1") (pinfunction "1_1") (pintype "passive"))
      (node (ref "U$1") (pin "D4") (pinfunction "D4_D4") (pintype "bidirectional"))
      (node (ref "U$1") (pin "D4_1") (pinfunction "D4_D4_1") (pintype "bidirectional"))
    )
    (net (code "73") (name "Net-(R317-Pad2)") (class "Default")
      (node (ref "R317") (pin "2") (pinfunction "2_2") (pintype "passive"))
      (node (ref "R413") (pin "1") (pinfunction "1_1") (pintype "passive"))
    )
    (net (code "74") (name "Net-(R318-Pad1)") (class "Default")
      (node (ref "R318") (pin "1") (pinfunction "1_1") (pintype "passive"))
      (node (ref "U$1") (pin "D5") (pinfunction "D5_D5") (pintype "bidirectional"))
      (node (ref "U$1") (pin "D5_1") (pinfunction "D5_D5_1") (pintype "bidirectional"))
    )
    (net (code "75") (name "Net-(R318-Pad2)") (class "Default")
      (node (ref "R318") (pin "2") (pinfunction "2_2") (pintype "passive"))
      (node (ref "R412") (pin "1") (pinfunction "1_1") (pintype "passive"))
    )
    (net (code "76") (name "Net-(R319-Pad1)") (class "Default")
      (node (ref "R319") (pin "1") (pinfunction "1_1") (pintype "passive"))
      (node (ref "U$1") (pin "D6") (pinfunction "D6_D6") (pintype "bidirectional"))
      (node (ref "U$1") (pin "D6_1") (pinfunction "D6_D6_1") (pintype "bidirectional"))
    )
    (net (code "77") (name "Net-(R319-Pad2)") (class "Default")
      (node (ref "R319") (pin "2") (pinfunction "2_2") (pintype "passive"))
      (node (ref "R411") (pin "1") (pinfunction "1_1") (pintype "passive"))
    )
    (net (code "78") (name "Net-(R320-Pad1)") (class "Default")
      (node (ref "R320") (pin "1") (pinfunction "1_1") (pintype "passive"))
      (node (ref "U$1") (pin "D7") (pinfunction "D7_D7") (pintype "bidirectional"))
      (node (ref "U$1") (pin "D7_1") (pinfunction "D7_D7_1") (pintype "bidirectional"))
    )
    (net (code "79") (name "Net-(R320-Pad2)") (class "Default")
      (node (ref "R320") (pin "2") (pinfunction "2_2") (pintype "passive"))
      (node (ref "R410") (pin "1") (pinfunction "1_1") (pintype "passive"))
    )
    (net (code "80") (name "Net-(T1-B)") (class "Default")
      (node (ref "R10") (pin "2") (pinfunction "2_2") (pintype "passive"))
      (node (ref "R5") (pin "2") (pinfunction "2_2") (pintype "passive"))
      (node (ref "T1") (pin "1") (pinfunction "B_1") (pintype "passive"))
    )
    (net (code "81") (name "Net-(T1-C)") (class "Default")
      (node (ref "JP7") (pin "1") (pinfunction "1_1") (pintype "passive"))
      (node (ref "T1") (pin "3") (pinfunction "C_3") (pintype "passive"))
    )
    (net (code "82") (name "Net-(T1-E)") (class "Default")
      (node (ref "JP8") (pin "1") (pinfunction "1_1") (pintype "passive"))
      (node (ref "T1") (pin "2") (pinfunction "E_2") (pintype "passive"))
    )
    (net (code "83") (name "Net-(T2-B)") (class "Default")
      (node (ref "R11") (pin "2") (pinfunction "2_2") (pintype "passive"))
      (node (ref "R9") (pin "2") (pinfunction "2_2") (pintype "passive"))
      (node (ref "T2") (pin "1") (pinfunction "B_1") (pintype "passive"))
    )
    (net (code "84") (name "Net-(T2-C)") (class "Default")
      (node (ref "JP9") (pin "1") (pinfunction "1_1") (pintype "passive"))
      (node (ref "T2") (pin "3") (pinfunction "C_3") (pintype "passive"))
    )
    (net (code "85") (name "Net-(T2-E)") (class "Default")
      (node (ref "JP10") (pin "1") (pinfunction "1_1") (pintype "passive"))
      (node (ref "T2") (pin "2") (pinfunction "E_2") (pintype "passive"))
    )
    (net (code "86") (name "Net-(U$1-PadRX)") (class "Default")
      (node (ref "U$1") (pin "RX") (pinfunction "RX_RX") (pintype "bidirectional"))
      (node (ref "U$1") (pin "RX_1") (pinfunction "RX_RX_1") (pintype "bidirectional"))
    )
    (net (code "87") (name "Net-(U$1-PadTX)") (class "Default")
      (node (ref "U$1") (pin "TX") (pinfunction "TX_TX") (pintype "bidirectional"))
      (node (ref "U$1") (pin "TX_1") (pinfunction "TX_TX_1") (pintype "bidirectional"))
    )
    (net (code "88") (name "Net-(U$1-~{RST}-PadRST)") (class "Default")
      (node (ref "U$1") (pin "RST") (pinfunction "~{RST}_RST") (pintype "bidirectional"))
      (node (ref "U$1") (pin "RST_1") (pinfunction "~{RST}_RST_1") (pintype "bidirectional"))
    )
    (net (code "89") (name "V_BATT") (class "Default")
      (node (ref "JP12") (pin "1") (pinfunction "1_1") (pintype "passive"))
      (node (ref "U$1") (pin "VBAT") (pinfunction "VBAT_VBAT") (pintype "passive"))
      (node (ref "U$1") (pin "VBATT_1") (pinfunction "VBAT_VBATT_1") (pintype "passive"))
    )
    (net (code "90") (name "unconnected-(JP1-Pad3)") (class "Default")
      (node (ref "JP1") (pin "3") (pinfunction "3_3") (pintype "passive"))
    )
    (net (code "91") (name "unconnected-(JP1-Pad4)") (class "Default")
      (node (ref "JP1") (pin "4") (pinfunction "4_4") (pintype "passive"))
    )
    (net (code "92") (name "unconnected-(JP1-Pad5)") (class "Default")
      (node (ref "JP1") (pin "5") (pinfunction "5_5") (pintype "passive"))
    )
    (net (code "93") (name "unconnected-(JP1-Pad6)") (class "Default")
      (node (ref "JP1") (pin "6") (pinfunction "6_6") (pintype "passive"))
    )
    (net (code "94") (name "unconnected-(JP1-Pad7)") (class "Default")
      (node (ref "JP1") (pin "7") (pinfunction "7_7") (pintype "passive"))
    )
    (net (code "95") (name "unconnected-(JP1-Pad8)") (class "Default")
      (node (ref "JP1") (pin "8") (pinfunction "8_8") (pintype "passive"))
    )
    (net (code "96") (name "unconnected-(JP1-Pad9)") (class "Default")
      (node (ref "JP1") (pin "9") (pinfunction "9_9") (pintype "passive"))
    )
    (net (code "97") (name "unconnected-(JP1-Pad10)") (class "Default")
      (node (ref "JP1") (pin "10") (pinfunction "10_10") (pintype "passive"))
    )
    (net (code "98") (name "unconnected-(JP1-Pad11)") (class "Default")
      (node (ref "JP1") (pin "11") (pinfunction "11_11") (pintype "passive"))
    )
    (net (code "99") (name "unconnected-(JP2-Pad1)") (class "Default")
      (node (ref "JP2") (pin "1") (pinfunction "1_1") (pintype "passive"))
    )
    (net (code "100") (name "unconnected-(JP2-Pad2)") (class "Default")
      (node (ref "JP2") (pin "2") (pinfunction "2_2") (pintype "passive"))
    )
    (net (code "101") (name "unconnected-(JP2-Pad3)") (class "Default")
      (node (ref "JP2") (pin "3") (pinfunction "3_3") (pintype "passive"))
    )
    (net (code "102") (name "unconnected-(JP2-Pad4)") (class "Default")
      (node (ref "JP2") (pin "4") (pinfunction "4_4") (pintype "passive"))
    )
    (net (code "103") (name "unconnected-(JP2-Pad5)") (class "Default")
      (node (ref "JP2") (pin "5") (pinfunction "5_5") (pintype "passive"))
    )
    (net (code "104") (name "unconnected-(JP2-Pad6)") (class "Default")
      (node (ref "JP2") (pin "6") (pinfunction "6_6") (pintype "passive"))
    )
    (net (code "105") (name "unconnected-(JP2-Pad7)") (class "Default")
      (node (ref "JP2") (pin "7") (pinfunction "7_7") (pintype "passive"))
    )
    (net (code "106") (name "unconnected-(JP2-Pad8)") (class "Default")
      (node (ref "JP2") (pin "8") (pinfunction "8_8") (pintype "passive"))
    )
    (net (code "107") (name "unconnected-(JP2-Pad9)") (class "Default")
      (node (ref "JP2") (pin "9") (pinfunction "9_9") (pintype "passive"))
    )
    (net (code "108") (name "unconnected-(JP2-Pad10)") (class "Default")
      (node (ref "JP2") (pin "10") (pinfunction "10_10") (pintype "passive"))
    )
    (net (code "109") (name "unconnected-(JP2-Pad11)") (class "Default")
      (node (ref "JP2") (pin "11") (pinfunction "11_11") (pintype "passive"))
    )
    (net (code "110") (name "unconnected-(JP2-Pad12)") (class "Default")
      (node (ref "JP2") (pin "12") (pinfunction "12_12") (pintype "passive"))
    )
    (net (code "111") (name "unconnected-(JP2-Pad13)") (class "Default")
      (node (ref "JP2") (pin "13") (pinfunction "13_13") (pintype "passive"))
    )
    (net (code "112") (name "unconnected-(JP3-D+-PadD+1)") (class "Default")
      (node (ref "JP3") (pin "D+1") (pinfunction "D+_D+1") (pintype "bidirectional"))
    )
    (net (code "113") (name "unconnected-(JP3-D--PadD-1)") (class "Default")
      (node (ref "JP3") (pin "D-1") (pinfunction "D-_D-1") (pintype "bidirectional"))
    )
    (net (code "114") (name "unconnected-(JP15-Pad1)") (class "Default")
      (node (ref "JP15") (pin "1") (pinfunction "1_1") (pintype "passive"))
    )
    (net (code "115") (name "unconnected-(JP15-Pad2)") (class "Default")
      (node (ref "JP15") (pin "2") (pinfunction "2_2") (pintype "passive"))
    )
    (net (code "116") (name "unconnected-(JP15-Pad3)") (class "Default")
      (node (ref "JP15") (pin "3") (pinfunction "3_3") (pintype "passive"))
    )
    (net (code "117") (name "unconnected-(JP15-Pad4)") (class "Default")
      (node (ref "JP15") (pin "4") (pinfunction "4_4") (pintype "passive"))
    )
    (net (code "118") (name "unconnected-(JP15-Pad5)") (class "Default")
      (node (ref "JP15") (pin "5") (pinfunction "5_5") (pintype "passive"))
    )
    (net (code "119") (name "unconnected-(JP15-Pad6)") (class "Default")
      (node (ref "JP15") (pin "6") (pinfunction "6_6") (pintype "passive"))
    )
    (net (code "120") (name "unconnected-(JP15-Pad7)") (class "Default")
      (node (ref "JP15") (pin "7") (pinfunction "7_7") (pintype "passive"))
    )
    (net (code "121") (name "unconnected-(JP15-Pad8)") (class "Default")
      (node (ref "JP15") (pin "8") (pinfunction "8_8") (pintype "passive"))
    )
    (net (code "122") (name "unconnected-(JP15-Pad9)") (class "Default")
      (node (ref "JP15") (pin "9") (pinfunction "9_9") (pintype "passive"))
    )
    (net (code "123") (name "unconnected-(JP15-Pad10)") (class "Default")
      (node (ref "JP15") (pin "10") (pinfunction "10_10") (pintype "passive"))
    )
    (net (code "124") (name "unconnected-(JP15-Pad11)") (class "Default")
      (node (ref "JP15") (pin "11") (pinfunction "11_11") (pintype "passive"))
    )
    (net (code "125") (name "unconnected-(JP15-Pad12)") (class "Default")
      (node (ref "JP15") (pin "12") (pinfunction "12_12") (pintype "passive"))
    )
    (net (code "126") (name "unconnected-(JP15-Pad13)") (class "Default")
      (node (ref "JP15") (pin "13") (pinfunction "13_13") (pintype "passive"))
    )
    (net (code "127") (name "unconnected-(JP16-Pad3)") (class "Default")
      (node (ref "JP16") (pin "3") (pinfunction "3_3") (pintype "passive"))
    )
    (net (code "128") (name "unconnected-(JP16-Pad4)") (class "Default")
      (node (ref "JP16") (pin "4") (pinfunction "4_4") (pintype "passive"))
    )
    (net (code "129") (name "unconnected-(JP16-Pad5)") (class "Default")
      (node (ref "JP16") (pin "5") (pinfunction "5_5") (pintype "passive"))
    )
    (net (code "130") (name "unconnected-(JP16-Pad6)") (class "Default")
      (node (ref "JP16") (pin "6") (pinfunction "6_6") (pintype "passive"))
    )
    (net (code "131") (name "unconnected-(JP16-Pad7)") (class "Default")
      (node (ref "JP16") (pin "7") (pinfunction "7_7") (pintype "passive"))
    )
    (net (code "132") (name "unconnected-(JP16-Pad8)") (class "Default")
      (node (ref "JP16") (pin "8") (pinfunction "8_8") (pintype "passive"))
    )
    (net (code "133") (name "unconnected-(JP16-Pad9)") (class "Default")
      (node (ref "JP16") (pin "9") (pinfunction "9_9") (pintype "passive"))
    )
    (net (code "134") (name "unconnected-(JP16-Pad10)") (class "Default")
      (node (ref "JP16") (pin "10") (pinfunction "10_10") (pintype "passive"))
    )
    (net (code "135") (name "unconnected-(JP16-Pad11)") (class "Default")
      (node (ref "JP16") (pin "11") (pinfunction "11_11") (pintype "passive"))
    )
    (net (code "136") (name "unconnected-(JP17-Pad3)") (class "Default")
      (node (ref "JP17") (pin "3") (pinfunction "3_3") (pintype "passive"))
    )
    (net (code "137") (name "unconnected-(JP17-Pad4)") (class "Default")
      (node (ref "JP17") (pin "4") (pinfunction "4_4") (pintype "passive"))
    )
    (net (code "138") (name "unconnected-(JP17-Pad5)") (class "Default")
      (node (ref "JP17") (pin "5") (pinfunction "5_5") (pintype "passive"))
    )
    (net (code "139") (name "unconnected-(JP17-Pad6)") (class "Default")
      (node (ref "JP17") (pin "6") (pinfunction "6_6") (pintype "passive"))
    )
    (net (code "140") (name "unconnected-(JP17-Pad7)") (class "Default")
      (node (ref "JP17") (pin "7") (pinfunction "7_7") (pintype "passive"))
    )
    (net (code "141") (name "unconnected-(JP17-Pad8)") (class "Default")
      (node (ref "JP17") (pin "8") (pinfunction "8_8") (pintype "passive"))
    )
    (net (code "142") (name "unconnected-(JP17-Pad9)") (class "Default")
      (node (ref "JP17") (pin "9") (pinfunction "9_9") (pintype "passive"))
    )
    (net (code "143") (name "unconnected-(JP17-Pad10)") (class "Default")
      (node (ref "JP17") (pin "10") (pinfunction "10_10") (pintype "passive"))
    )
    (net (code "144") (name "unconnected-(JP17-Pad11)") (class "Default")
      (node (ref "JP17") (pin "11") (pinfunction "11_11") (pintype "passive"))
    )
    (net (code "145") (name "unconnected-(JP18-Pad3)") (class "Default")
      (node (ref "JP18") (pin "3") (pinfunction "3_3") (pintype "passive"))
    )
    (net (code "146") (name "unconnected-(JP18-Pad4)") (class "Default")
      (node (ref "JP18") (pin "4") (pinfunction "4_4") (pintype "passive"))
    )
    (net (code "147") (name "unconnected-(JP18-Pad5)") (class "Default")
      (node (ref "JP18") (pin "5") (pinfunction "5_5") (pintype "passive"))
    )
    (net (code "148") (name "unconnected-(JP18-Pad6)") (class "Default")
      (node (ref "JP18") (pin "6") (pinfunction "6_6") (pintype "passive"))
    )
    (net (code "149") (name "unconnected-(JP18-Pad7)") (class "Default")
      (node (ref "JP18") (pin "7") (pinfunction "7_7") (pintype "passive"))
    )
    (net (code "150") (name "unconnected-(JP18-Pad8)") (class "Default")
      (node (ref "JP18") (pin "8") (pinfunction "8_8") (pintype "passive"))
    )
    (net (code "151") (name "unconnected-(JP18-Pad9)") (class "Default")
      (node (ref "JP18") (pin "9") (pinfunction "9_9") (pintype "passive"))
    )
    (net (code "152") (name "unconnected-(JP18-Pad10)") (class "Default")
      (node (ref "JP18") (pin "10") (pinfunction "10_10") (pintype "passive"))
    )
    (net (code "153") (name "unconnected-(JP18-Pad11)") (class "Default")
      (node (ref "JP18") (pin "11") (pinfunction "11_11") (pintype "passive"))
    )
    (net (code "154") (name "unconnected-(JP19-Pad3)") (class "Default")
      (node (ref "JP19") (pin "3") (pinfunction "3_3") (pintype "passive"))
    )
    (net (code "155") (name "unconnected-(JP19-Pad4)") (class "Default")
      (node (ref "JP19") (pin "4") (pinfunction "4_4") (pintype "passive"))
    )
    (net (code "156") (name "unconnected-(JP19-Pad5)") (class "Default")
      (node (ref "JP19") (pin "5") (pinfunction "5_5") (pintype "passive"))
    )
    (net (code "157") (name "unconnected-(JP19-Pad6)") (class "Default")
      (node (ref "JP19") (pin "6") (pinfunction "6_6") (pintype "passive"))
    )
    (net (code "158") (name "unconnected-(JP19-Pad7)") (class "Default")
      (node (ref "JP19") (pin "7") (pinfunction "7_7") (pintype "passive"))
    )
    (net (code "159") (name "unconnected-(JP19-Pad8)") (class "Default")
      (node (ref "JP19") (pin "8") (pinfunction "8_8") (pintype "passive"))
    )
    (net (code "160") (name "unconnected-(JP19-Pad9)") (class "Default")
      (node (ref "JP19") (pin "9") (pinfunction "9_9") (pintype "passive"))
    )
    (net (code "161") (name "unconnected-(JP19-Pad10)") (class "Default")
      (node (ref "JP19") (pin "10") (pinfunction "10_10") (pintype "passive"))
    )
    (net (code "162") (name "unconnected-(JP19-Pad11)") (class "Default")
      (node (ref "JP19") (pin "11") (pinfunction "11_11") (pintype "passive"))
    )
    (net (code "163") (name "unconnected-(JP20-Pad3)") (class "Default")
      (node (ref "JP20") (pin "3") (pinfunction "3_3") (pintype "passive"))
    )
    (net (code "164") (name "unconnected-(JP20-Pad4)") (class "Default")
      (node (ref "JP20") (pin "4") (pinfunction "4_4") (pintype "passive"))
    )
    (net (code "165") (name "unconnected-(JP20-Pad5)") (class "Default")
      (node (ref "JP20") (pin "5") (pinfunction "5_5") (pintype "passive"))
    )
    (net (code "166") (name "unconnected-(JP20-Pad6)") (class "Default")
      (node (ref "JP20") (pin "6") (pinfunction "6_6") (pintype "passive"))
    )
    (net (code "167") (name "unconnected-(JP20-Pad7)") (class "Default")
      (node (ref "JP20") (pin "7") (pinfunction "7_7") (pintype "passive"))
    )
    (net (code "168") (name "unconnected-(JP20-Pad8)") (class "Default")
      (node (ref "JP20") (pin "8") (pinfunction "8_8") (pintype "passive"))
    )
    (net (code "169") (name "unconnected-(JP20-Pad9)") (class "Default")
      (node (ref "JP20") (pin "9") (pinfunction "9_9") (pintype "passive"))
    )
    (net (code "170") (name "unconnected-(JP20-Pad10)") (class "Default")
      (node (ref "JP20") (pin "10") (pinfunction "10_10") (pintype "passive"))
    )
    (net (code "171") (name "unconnected-(JP20-Pad11)") (class "Default")
      (node (ref "JP20") (pin "11") (pinfunction "11_11") (pintype "passive"))
    )
    (net (code "172") (name "unconnected-(JP21-Pad3)") (class "Default")
      (node (ref "JP21") (pin "3") (pinfunction "3_3") (pintype "passive"))
    )
    (net (code "173") (name "unconnected-(JP21-Pad4)") (class "Default")
      (node (ref "JP21") (pin "4") (pinfunction "4_4") (pintype "passive"))
    )
    (net (code "174") (name "unconnected-(JP21-Pad5)") (class "Default")
      (node (ref "JP21") (pin "5") (pinfunction "5_5") (pintype "passive"))
    )
    (net (code "175") (name "unconnected-(JP21-Pad6)") (class "Default")
      (node (ref "JP21") (pin "6") (pinfunction "6_6") (pintype "passive"))
    )
    (net (code "176") (name "unconnected-(JP21-Pad7)") (class "Default")
      (node (ref "JP21") (pin "7") (pinfunction "7_7") (pintype "passive"))
    )
    (net (code "177") (name "unconnected-(JP21-Pad8)") (class "Default")
      (node (ref "JP21") (pin "8") (pinfunction "8_8") (pintype "passive"))
    )
    (net (code "178") (name "unconnected-(JP21-Pad9)") (class "Default")
      (node (ref "JP21") (pin "9") (pinfunction "9_9") (pintype "passive"))
    )
    (net (code "179") (name "unconnected-(JP21-Pad10)") (class "Default")
      (node (ref "JP21") (pin "10") (pinfunction "10_10") (pintype "passive"))
    )
    (net (code "180") (name "unconnected-(JP21-Pad11)") (class "Default")
      (node (ref "JP21") (pin "11") (pinfunction "11_11") (pintype "passive"))
    )
    (net (code "181") (name "unconnected-(JP22-Pad3)") (class "Default")
      (node (ref "JP22") (pin "3") (pinfunction "3_3") (pintype "passive"))
    )
    (net (code "182") (name "unconnected-(JP22-Pad4)") (class "Default")
      (node (ref "JP22") (pin "4") (pinfunction "4_4") (pintype "passive"))
    )
    (net (code "183") (name "unconnected-(JP22-Pad5)") (class "Default")
      (node (ref "JP22") (pin "5") (pinfunction "5_5") (pintype "passive"))
    )
    (net (code "184") (name "unconnected-(JP22-Pad6)") (class "Default")
      (node (ref "JP22") (pin "6") (pinfunction "6_6") (pintype "passive"))
    )
    (net (code "185") (name "unconnected-(JP22-Pad7)") (class "Default")
      (node (ref "JP22") (pin "7") (pinfunction "7_7") (pintype "passive"))
    )
    (net (code "186") (name "unconnected-(JP22-Pad8)") (class "Default")
      (node (ref "JP22") (pin "8") (pinfunction "8_8") (pintype "passive"))
    )
    (net (code "187") (name "unconnected-(JP22-Pad9)") (class "Default")
      (node (ref "JP22") (pin "9") (pinfunction "9_9") (pintype "passive"))
    )
    (net (code "188") (name "unconnected-(JP22-Pad10)") (class "Default")
      (node (ref "JP22") (pin "10") (pinfunction "10_10") (pintype "passive"))
    )
    (net (code "189") (name "unconnected-(JP22-Pad11)") (class "Default")
      (node (ref "JP22") (pin "11") (pinfunction "11_11") (pintype "passive"))
    )
    (net (code "190") (name "unconnected-(JP203-Pad1)") (class "Default")
      (node (ref "JP203") (pin "1") (pinfunction "1_1") (pintype "passive"))
    )
    (net (code "191") (name "unconnected-(JP203-Pad2)") (class "Default")
      (node (ref "JP203") (pin "2") (pinfunction "2_2") (pintype "passive"))
    )
    (net (code "192") (name "unconnected-(JP203-Pad3)") (class "Default")
      (node (ref "JP203") (pin "3") (pinfunction "3_3") (pintype "passive"))
    )
    (net (code "193") (name "unconnected-(JP203-Pad4)") (class "Default")
      (node (ref "JP203") (pin "4") (pinfunction "4_4") (pintype "passive"))
    )
    (net (code "194") (name "unconnected-(JP203-Pad5)") (class "Default")
      (node (ref "JP203") (pin "5") (pinfunction "5_5") (pintype "passive"))
    )
    (net (code "195") (name "unconnected-(JP203-Pad6)") (class "Default")
      (node (ref "JP203") (pin "6") (pinfunction "6_6") (pintype "passive"))
    )
    (net (code "196") (name "unconnected-(JP203-Pad7)") (class "Default")
      (node (ref "JP203") (pin "7") (pinfunction "7_7") (pintype "passive"))
    )
    (net (code "197") (name "unconnected-(JP203-Pad8)") (class "Default")
      (node (ref "JP203") (pin "8") (pinfunction "8_8") (pintype "passive"))
    )
    (net (code "198") (name "unconnected-(JP203-Pad9)") (class "Default")
      (node (ref "JP203") (pin "9") (pinfunction "9_9") (pintype "passive"))
    )
    (net (code "199") (name "unconnected-(JP203-Pad10)") (class "Default")
      (node (ref "JP203") (pin "10") (pinfunction "10_10") (pintype "passive"))
    )
    (net (code "200") (name "unconnected-(JP203-Pad11)") (class "Default")
      (node (ref "JP203") (pin "11") (pinfunction "11_11") (pintype "passive"))
    )
    (net (code "201") (name "unconnected-(JP203-Pad12)") (class "Default")
      (node (ref "JP203") (pin "12") (pinfunction "12_12") (pintype "passive"))
    )
    (net (code "202") (name "unconnected-(JP203-Pad13)") (class "Default")
      (node (ref "JP203") (pin "13") (pinfunction "13_13") (pintype "passive"))
    )
    (net (code "203") (name "unconnected-(JP204-Pad1)") (class "Default")
      (node (ref "JP204") (pin "1") (pinfunction "1_1") (pintype "passive"))
    )
    (net (code "204") (name "unconnected-(JP204-Pad2)") (class "Default")
      (node (ref "JP204") (pin "2") (pinfunction "2_2") (pintype "passive"))
    )
    (net (code "205") (name "unconnected-(JP204-Pad3)") (class "Default")
      (node (ref "JP204") (pin "3") (pinfunction "3_3") (pintype "passive"))
    )
    (net (code "206") (name "unconnected-(JP204-Pad4)") (class "Default")
      (node (ref "JP204") (pin "4") (pinfunction "4_4") (pintype "passive"))
    )
    (net (code "207") (name "unconnected-(JP204-Pad5)") (class "Default")
      (node (ref "JP204") (pin "5") (pinfunction "5_5") (pintype "passive"))
    )
    (net (code "208") (name "unconnected-(JP204-Pad6)") (class "Default")
      (node (ref "JP204") (pin "6") (pinfunction "6_6") (pintype "passive"))
    )
    (net (code "209") (name "unconnected-(JP204-Pad7)") (class "Default")
      (node (ref "JP204") (pin "7") (pinfunction "7_7") (pintype "passive"))
    )
    (net (code "210") (name "unconnected-(JP204-Pad8)") (class "Default")
      (node (ref "JP204") (pin "8") (pinfunction "8_8") (pintype "passive"))
    )
    (net (code "211") (name "unconnected-(JP204-Pad9)") (class "Default")
      (node (ref "JP204") (pin "9") (pinfunction "9_9") (pintype "passive"))
    )
    (net (code "212") (name "unconnected-(JP204-Pad10)") (class "Default")
      (node (ref "JP204") (pin "10") (pinfunction "10_10") (pintype "passive"))
    )
    (net (code "213") (name "unconnected-(JP204-Pad11)") (class "Default")
      (node (ref "JP204") (pin "11") (pinfunction "11_11") (pintype "passive"))
    )
    (net (code "214") (name "unconnected-(JP204-Pad12)") (class "Default")
      (node (ref "JP204") (pin "12") (pinfunction "12_12") (pintype "passive"))
    )
    (net (code "215") (name "unconnected-(JP204-Pad13)") (class "Default")
      (node (ref "JP204") (pin "13") (pinfunction "13_13") (pintype "passive"))
    )
    (net (code "216") (name "unconnected-(JP213-Pad1)") (class "Default")
      (node (ref "JP213") (pin "1") (pinfunction "1_1") (pintype "passive"))
    )
    (net (code "217") (name "unconnected-(JP213-Pad2)") (class "Default")
      (node (ref "JP213") (pin "2") (pinfunction "2_2") (pintype "passive"))
    )
    (net (code "218") (name "unconnected-(JP213-Pad3)") (class "Default")
      (node (ref "JP213") (pin "3") (pinfunction "3_3") (pintype "passive"))
    )
    (net (code "219") (name "unconnected-(JP213-Pad4)") (class "Default")
      (node (ref "JP213") (pin "4") (pinfunction "4_4") (pintype "passive"))
    )
    (net (code "220") (name "unconnected-(JP213-Pad5)") (class "Default")
      (node (ref "JP213") (pin "5") (pinfunction "5_5") (pintype "passive"))
    )
    (net (code "221") (name "unconnected-(JP213-Pad6)") (class "Default")
      (node (ref "JP213") (pin "6") (pinfunction "6_6") (pintype "passive"))
    )
    (net (code "222") (name "unconnected-(JP213-Pad7)") (class "Default")
      (node (ref "JP213") (pin "7") (pinfunction "7_7") (pintype "passive"))
    )
    (net (code "223") (name "unconnected-(JP213-Pad8)") (class "Default")
      (node (ref "JP213") (pin "8") (pinfunction "8_8") (pintype "passive"))
    )
    (net (code "224") (name "unconnected-(JP213-Pad9)") (class "Default")
      (node (ref "JP213") (pin "9") (pinfunction "9_9") (pintype "passive"))
    )
    (net (code "225") (name "unconnected-(JP213-Pad10)") (class "Default")
      (node (ref "JP213") (pin "10") (pinfunction "10_10") (pintype "passive"))
    )
    (net (code "226") (name "unconnected-(JP213-Pad11)") (class "Default")
      (node (ref "JP213") (pin "11") (pinfunction "11_11") (pintype "passive"))
    )
    (net (code "227") (name "unconnected-(JP213-Pad12)") (class "Default")
      (node (ref "JP213") (pin "12") (pinfunction "12_12") (pintype "passive"))
    )
    (net (code "228") (name "unconnected-(JP213-Pad13)") (class "Default")
      (node (ref "JP213") (pin "13") (pinfunction "13_13") (pintype "passive"))
    )
    (net (code "229") (name "unconnected-(JP214-Pad1)") (class "Default")
      (node (ref "JP214") (pin "1") (pinfunction "1_1") (pintype "passive"))
    )
    (net (code "230") (name "unconnected-(JP214-Pad2)") (class "Default")
      (node (ref "JP214") (pin "2") (pinfunction "2_2") (pintype "passive"))
    )
    (net (code "231") (name "unconnected-(JP214-Pad3)") (class "Default")
      (node (ref "JP214") (pin "3") (pinfunction "3_3") (pintype "passive"))
    )
    (net (code "232") (name "unconnected-(JP214-Pad4)") (class "Default")
      (node (ref "JP214") (pin "4") (pinfunction "4_4") (pintype "passive"))
    )
    (net (code "233") (name "unconnected-(JP214-Pad5)") (class "Default")
      (node (ref "JP214") (pin "5") (pinfunction "5_5") (pintype "passive"))
    )
    (net (code "234") (name "unconnected-(JP214-Pad6)") (class "Default")
      (node (ref "JP214") (pin "6") (pinfunction "6_6") (pintype "passive"))
    )
    (net (code "235") (name "unconnected-(JP214-Pad7)") (class "Default")
      (node (ref "JP214") (pin "7") (pinfunction "7_7") (pintype "passive"))
    )
    (net (code "236") (name "unconnected-(JP214-Pad8)") (class "Default")
      (node (ref "JP214") (pin "8") (pinfunction "8_8") (pintype "passive"))
    )
    (net (code "237") (name "unconnected-(JP214-Pad9)") (class "Default")
      (node (ref "JP214") (pin "9") (pinfunction "9_9") (pintype "passive"))
    )
    (net (code "238") (name "unconnected-(JP214-Pad10)") (class "Default")
      (node (ref "JP214") (pin "10") (pinfunction "10_10") (pintype "passive"))
    )
    (net (code "239") (name "unconnected-(JP214-Pad11)") (class "Default")
      (node (ref "JP214") (pin "11") (pinfunction "11_11") (pintype "passive"))
    )
    (net (code "240") (name "unconnected-(JP214-Pad12)") (class "Default")
      (node (ref "JP214") (pin "12") (pinfunction "12_12") (pintype "passive"))
    )
    (net (code "241") (name "unconnected-(JP214-Pad13)") (class "Default")
      (node (ref "JP214") (pin "13") (pinfunction "13_13") (pintype "passive"))
    )
  )
)
